# HandHeld_Terminal_V2_Rev3.net
KiCad netlist of a schematic drawn in Altium Designer
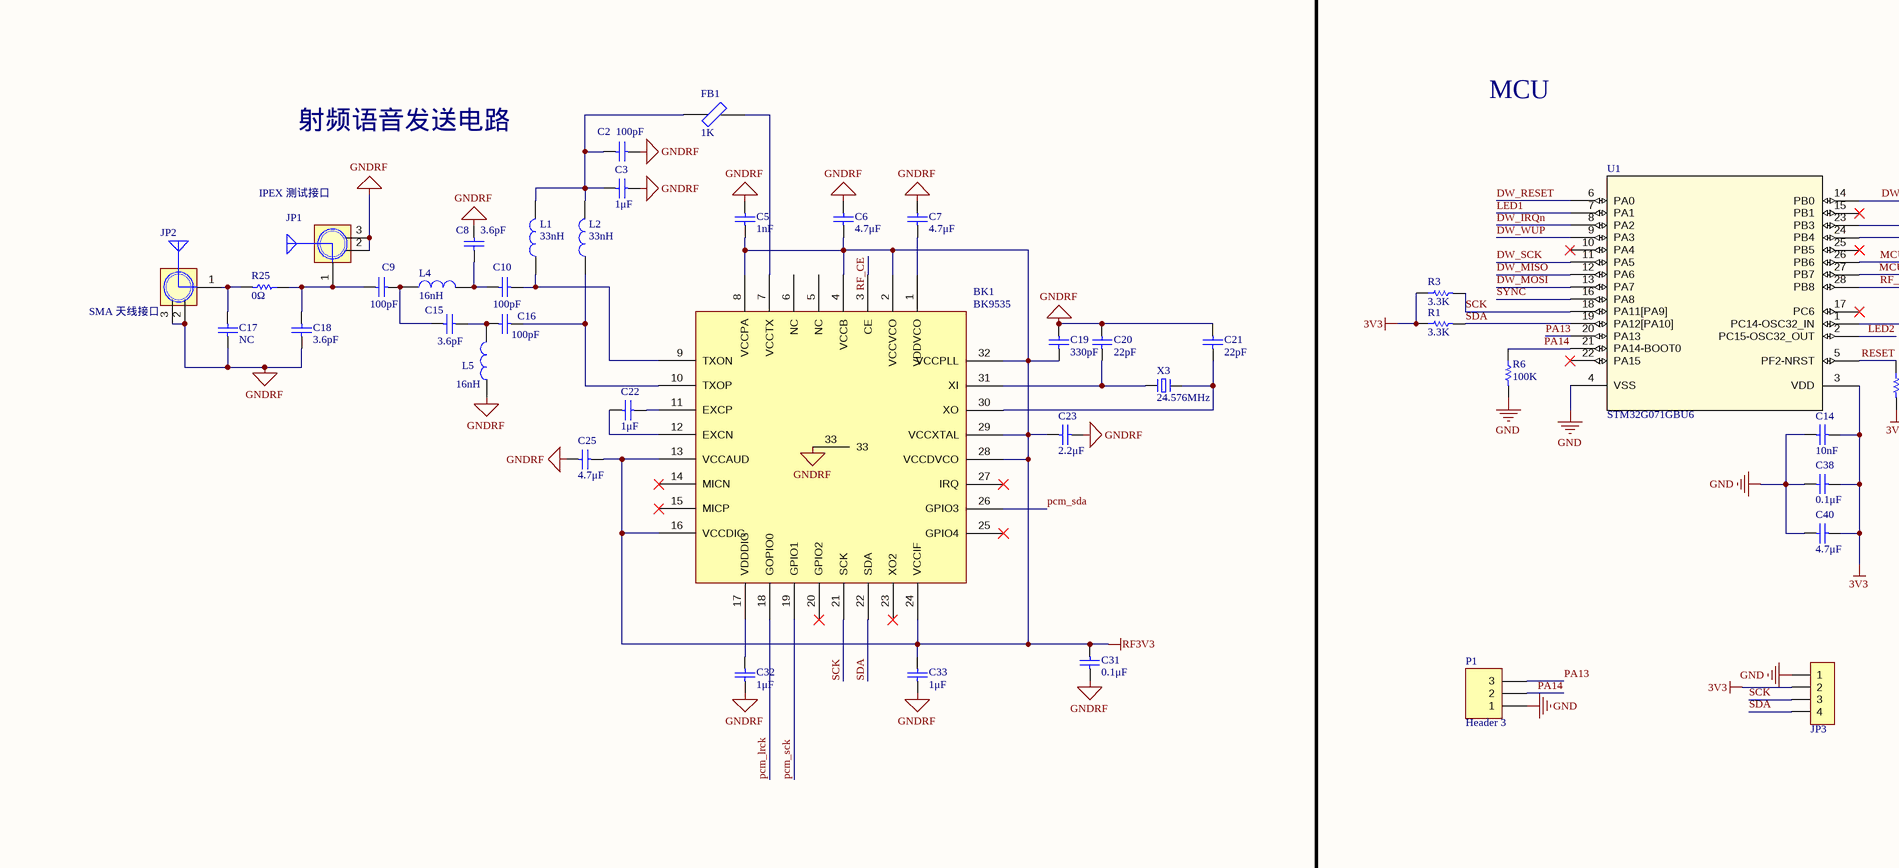
[diagram p0: HandHeld_Terminal_V2_Rev3.SchDoc, top left]
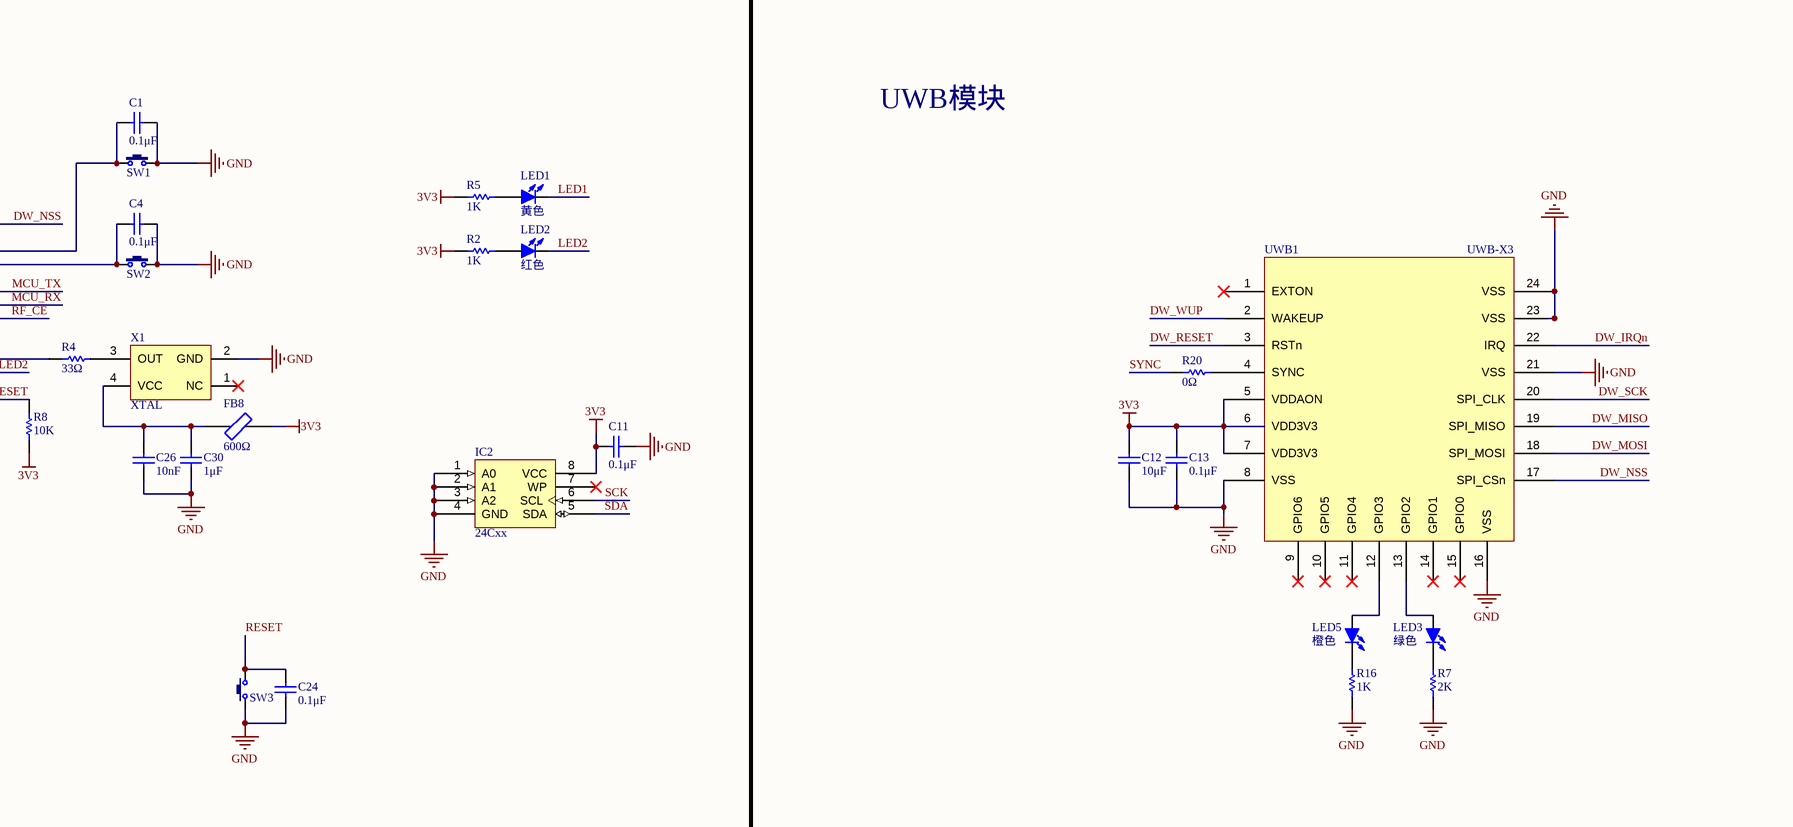
[diagram p1: HandHeld_Terminal_V2_Rev3.SchDoc, top right]
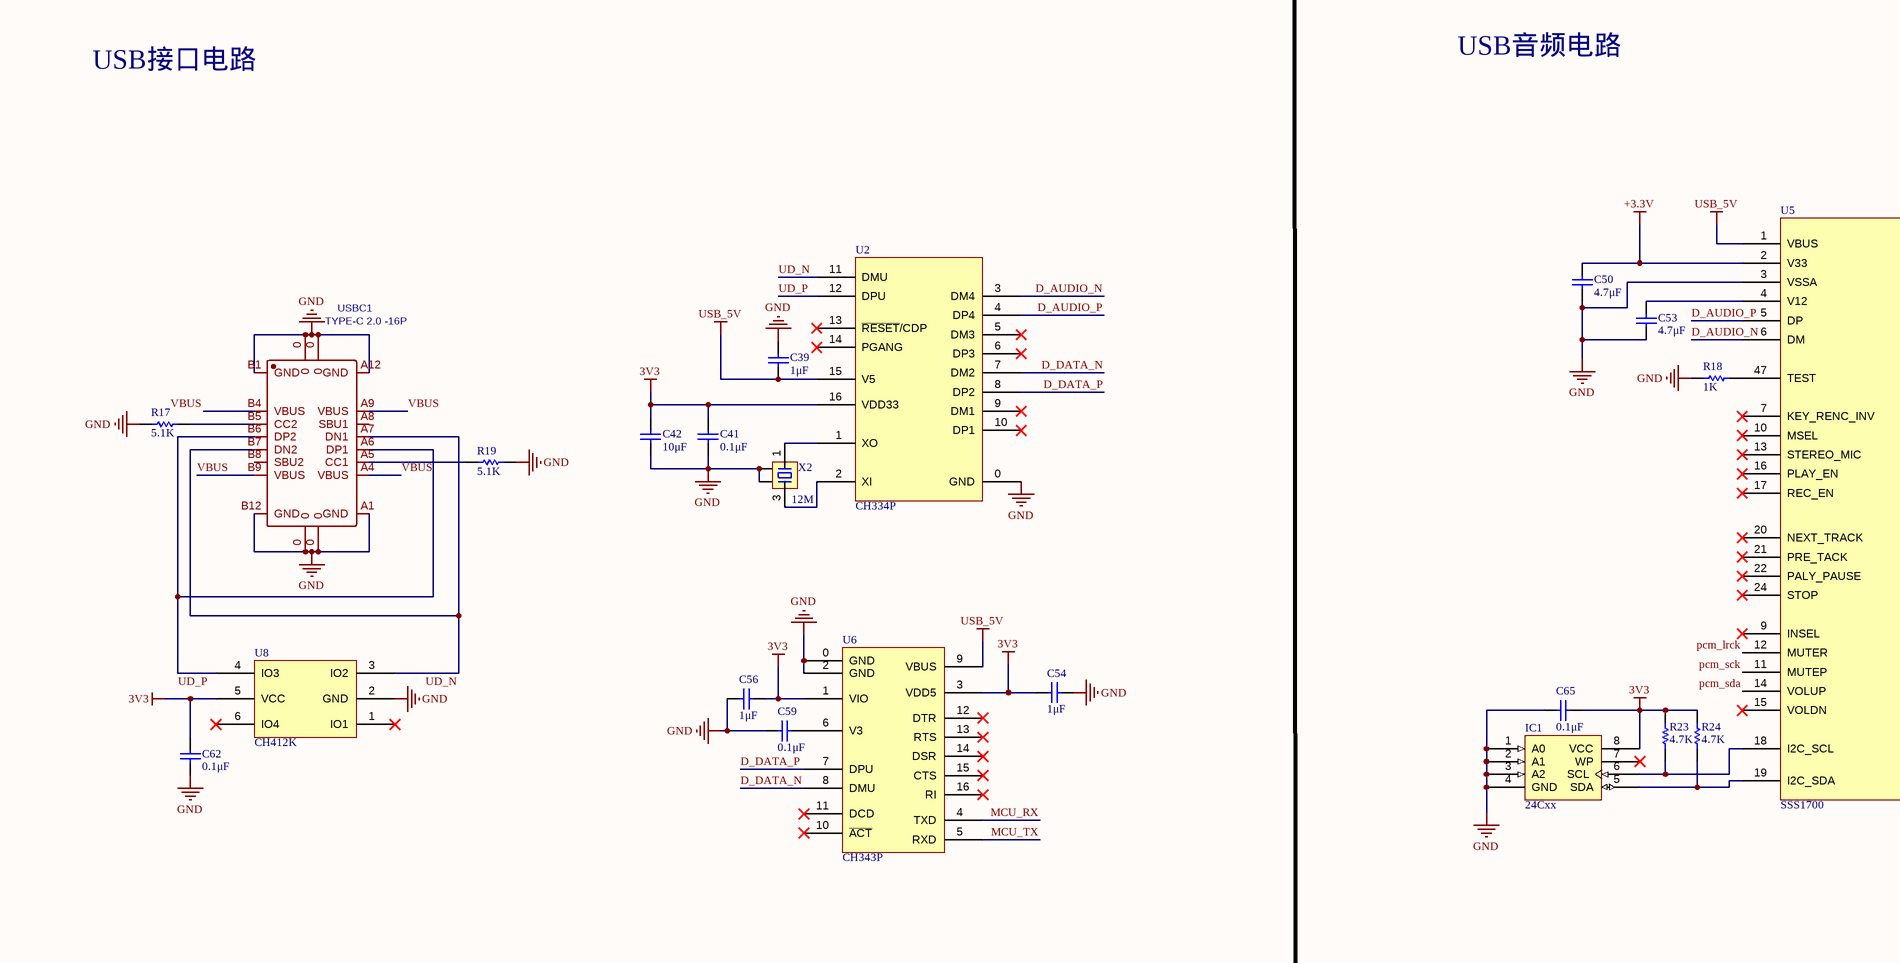
[diagram p2: HandHeld_Terminal_V2_Rev3.SchDoc, bottom left]
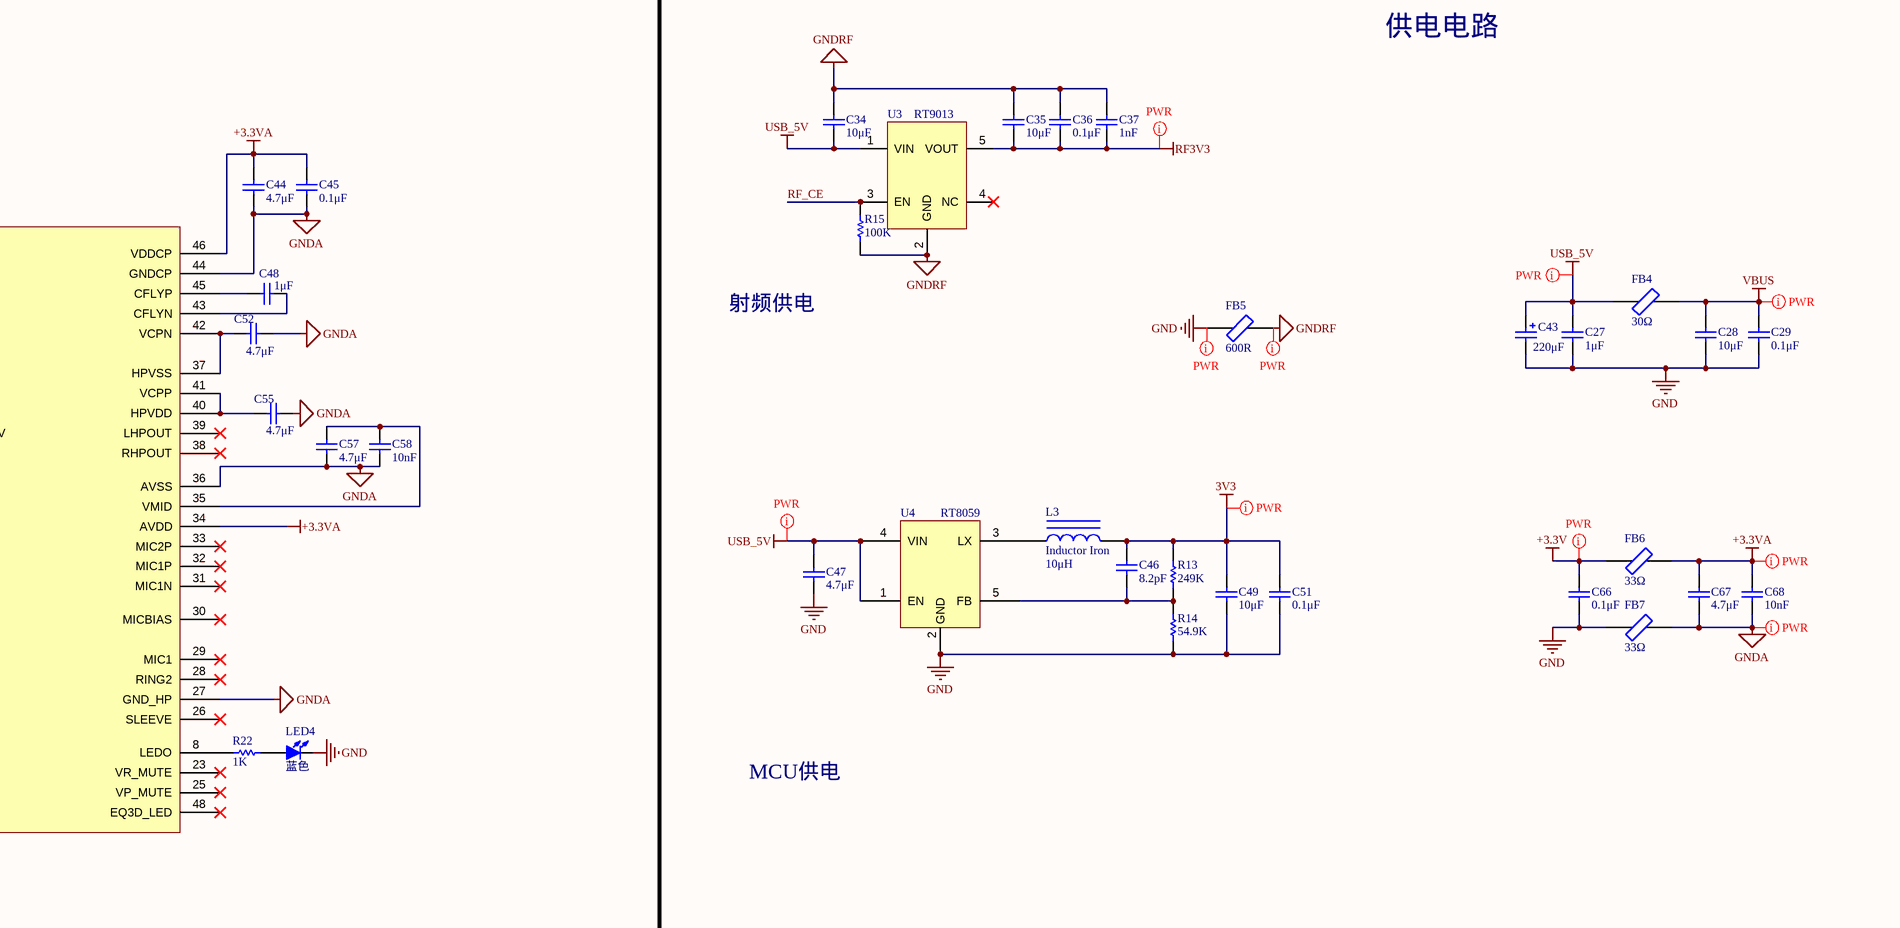
[diagram p3: HandHeld_Terminal_V2_Rev3.SchDoc, bottom right]

(export (version "E")
  (design (tool "Eeschema 10.0.6"))
  (components
    (comp (ref "BK1") (value "BK9535") (footprint "QFN32 5x5_N") (libsource (lib "Nixie") (part "BK9530")))
    (comp (ref "C1")
      (value "0.1μF")
      (footprint "C 0603_L")
      (description "Capacitor")
      (fields (field (name "Comment") "Cap") (field (name "PUBLISHER") "Altium Limited"))
      (libsource (lib "Nixie") (part "Cap"))
    )
    (comp (ref "C2")
      (value "100pF")
      (footprint "C 0603_L")
      (description "Capacitor")
      (fields (field (name "Comment") "Cap") (field (name "PUBLISHER") "Altium Limited"))
      (libsource (lib "Nixie") (part "Cap"))
    )
    (comp (ref "C3")
      (value "1μF")
      (footprint "C 0603_L")
      (description "Capacitor")
      (fields (field (name "Comment") "Cap") (field (name "PUBLISHER") "Altium Limited"))
      (libsource (lib "Nixie") (part "Cap"))
    )
    (comp (ref "C4")
      (value "0.1μF")
      (footprint "C 0603_L")
      (description "Capacitor")
      (fields (field (name "Comment") "Cap") (field (name "PUBLISHER") "Altium Limited"))
      (libsource (lib "Nixie") (part "Cap"))
    )
    (comp (ref "C5")
      (value "1nF")
      (footprint "C 0603_L")
      (description "Capacitor")
      (fields (field (name "Comment") "Cap") (field (name "PUBLISHER") "Altium Limited"))
      (libsource (lib "Nixie") (part "Cap"))
    )
    (comp (ref "C6")
      (value "4.7μF")
      (footprint "C 0603_L")
      (description "Capacitor")
      (fields (field (name "Comment") "Cap") (field (name "PUBLISHER") "Altium Limited"))
      (libsource (lib "Nixie") (part "Cap"))
    )
    (comp (ref "C7")
      (value "4.7μF")
      (footprint "C 0603_L")
      (description "Capacitor")
      (fields (field (name "Comment") "Cap") (field (name "PUBLISHER") "Altium Limited"))
      (libsource (lib "Nixie") (part "Cap"))
    )
    (comp (ref "C8")
      (value "3.6pF")
      (footprint "C 0603_L")
      (description "Capacitor")
      (fields (field (name "Comment") "Cap") (field (name "PUBLISHER") "Altium Limited"))
      (libsource (lib "Nixie") (part "Cap"))
    )
    (comp (ref "C9")
      (value "100pF")
      (footprint "C 0603_L")
      (description "Capacitor")
      (fields (field (name "Comment") "Cap") (field (name "PUBLISHER") "Altium Limited"))
      (libsource (lib "Nixie") (part "Cap"))
    )
    (comp (ref "C10")
      (value "100pF")
      (footprint "C 0603_L")
      (description "Capacitor")
      (fields (field (name "Comment") "Cap") (field (name "PUBLISHER") "Altium Limited"))
      (libsource (lib "Nixie") (part "Cap"))
    )
    (comp (ref "C11")
      (value "0.1μF")
      (footprint "C 0603_L")
      (description "Capacitor")
      (fields (field (name "Comment") "Cap") (field (name "PUBLISHER") "Altium Limited"))
      (libsource (lib "Nixie") (part "Cap"))
    )
    (comp (ref "C12")
      (value "10μF")
      (footprint "C 0603_L")
      (description "Capacitor")
      (fields (field (name "Comment") "Cap") (field (name "PUBLISHER") "Altium Limited"))
      (libsource (lib "Nixie") (part "Cap"))
    )
    (comp (ref "C13")
      (value "0.1μF")
      (footprint "C 0603_L")
      (description "Capacitor")
      (fields (field (name "Comment") "Cap") (field (name "PUBLISHER") "Altium Limited"))
      (libsource (lib "Nixie") (part "Cap"))
    )
    (comp (ref "C14")
      (value "10nF")
      (footprint "C 0603_L")
      (description "Capacitor")
      (fields (field (name "Comment") "Cap") (field (name "PUBLISHER") "Altium Limited"))
      (libsource (lib "Nixie") (part "Cap"))
    )
    (comp (ref "C15")
      (value "3.6pF")
      (footprint "C 0603_L")
      (description "Capacitor")
      (fields (field (name "Comment") "Cap") (field (name "PUBLISHER") "Altium Limited"))
      (libsource (lib "Nixie") (part "Cap"))
    )
    (comp (ref "C16")
      (value "100pF")
      (footprint "C 0603_L")
      (description "Capacitor")
      (fields (field (name "Comment") "Cap") (field (name "PUBLISHER") "Altium Limited"))
      (libsource (lib "Nixie") (part "Cap"))
    )
    (comp (ref "C17")
      (value "NC")
      (footprint "C 0603_L")
      (description "Capacitor")
      (fields (field (name "Comment") "Cap") (field (name "PUBLISHER") "Altium Limited"))
      (libsource (lib "Nixie") (part "Cap"))
    )
    (comp (ref "C18")
      (value "3.6pF")
      (footprint "C 0603_L")
      (description "Capacitor")
      (fields (field (name "Comment") "Cap") (field (name "PUBLISHER") "Altium Limited"))
      (libsource (lib "Nixie") (part "Cap"))
    )
    (comp (ref "C19")
      (value "330pF")
      (footprint "C 0603_L")
      (description "Capacitor")
      (fields (field (name "Comment") "Cap") (field (name "PUBLISHER") "Altium Limited"))
      (libsource (lib "Nixie") (part "Cap"))
    )
    (comp (ref "C20")
      (value "22pF")
      (footprint "C 0603_L")
      (description "Capacitor")
      (fields (field (name "Comment") "Cap") (field (name "PUBLISHER") "Altium Limited"))
      (libsource (lib "Nixie") (part "Cap"))
    )
    (comp (ref "C21")
      (value "22pF")
      (footprint "C 0603_L")
      (description "Capacitor")
      (fields (field (name "Comment") "Cap") (field (name "PUBLISHER") "Altium Limited"))
      (libsource (lib "Nixie") (part "Cap"))
    )
    (comp (ref "C22")
      (value "1μF")
      (footprint "C 0603_L")
      (description "Capacitor")
      (fields (field (name "Comment") "Cap") (field (name "PUBLISHER") "Altium Limited"))
      (libsource (lib "Nixie") (part "Cap"))
    )
    (comp (ref "C23")
      (value "2.2μF")
      (footprint "C 0603_L")
      (description "Capacitor")
      (fields (field (name "Comment") "Cap") (field (name "PUBLISHER") "Altium Limited"))
      (libsource (lib "Nixie") (part "Cap"))
    )
    (comp (ref "C24")
      (value "0.1μF")
      (footprint "C 0603_L")
      (description "Capacitor")
      (fields (field (name "Comment") "Cap") (field (name "PUBLISHER") "Altium Limited"))
      (libsource (lib "Nixie") (part "Cap"))
    )
    (comp (ref "C25")
      (value "4.7μF")
      (footprint "C 0603_L")
      (description "Capacitor")
      (fields (field (name "Comment") "Cap") (field (name "PUBLISHER") "Altium Limited"))
      (libsource (lib "Nixie") (part "Cap"))
    )
    (comp (ref "C26")
      (value "10nF")
      (footprint "C 0603_L")
      (description "Capacitor")
      (fields (field (name "Comment") "Cap") (field (name "PUBLISHER") "Altium Limited"))
      (libsource (lib "Nixie") (part "Cap"))
    )
    (comp (ref "C27")
      (value "1μF")
      (footprint "C 0603_L")
      (description "Capacitor")
      (fields (field (name "Comment") "Cap") (field (name "PUBLISHER") "Altium Limited"))
      (libsource (lib "Nixie") (part "Cap"))
    )
    (comp (ref "C28")
      (value "10μF")
      (footprint "C 0603_L")
      (description "Capacitor")
      (fields (field (name "Comment") "Cap") (field (name "PUBLISHER") "Altium Limited"))
      (libsource (lib "Nixie") (part "Cap"))
    )
    (comp (ref "C29")
      (value "0.1μF")
      (footprint "C 0603_L")
      (description "Capacitor")
      (fields (field (name "Comment") "Cap") (field (name "PUBLISHER") "Altium Limited"))
      (libsource (lib "Nixie") (part "Cap"))
    )
    (comp (ref "C30")
      (value "1μF")
      (footprint "C 0603_L")
      (description "Capacitor")
      (fields (field (name "Comment") "Cap") (field (name "PUBLISHER") "Altium Limited"))
      (libsource (lib "Nixie") (part "Cap"))
    )
    (comp (ref "C31")
      (value "0.1μF")
      (footprint "C 0603_L")
      (description "Capacitor")
      (fields (field (name "Comment") "Cap") (field (name "PUBLISHER") "Altium Limited"))
      (libsource (lib "Nixie") (part "Cap"))
    )
    (comp (ref "C32")
      (value "1μF")
      (footprint "C 0603_L")
      (description "Capacitor")
      (fields (field (name "Comment") "Cap") (field (name "PUBLISHER") "Altium Limited"))
      (libsource (lib "Nixie") (part "Cap"))
    )
    (comp (ref "C33")
      (value "1μF")
      (footprint "C 0603_L")
      (description "Capacitor")
      (fields (field (name "Comment") "Cap") (field (name "PUBLISHER") "Altium Limited"))
      (libsource (lib "Nixie") (part "Cap"))
    )
    (comp (ref "C34")
      (value "10μF")
      (footprint "C 0603_L")
      (description "Capacitor")
      (fields (field (name "Comment") "Cap") (field (name "PUBLISHER") "Altium Limited"))
      (libsource (lib "Nixie") (part "Cap"))
    )
    (comp (ref "C35")
      (value "10μF")
      (footprint "C 0603_L")
      (description "Capacitor")
      (fields (field (name "Comment") "Cap") (field (name "PUBLISHER") "Altium Limited"))
      (libsource (lib "Nixie") (part "Cap"))
    )
    (comp (ref "C36")
      (value "0.1μF")
      (footprint "C 0603_L")
      (description "Capacitor")
      (fields (field (name "Comment") "Cap") (field (name "PUBLISHER") "Altium Limited"))
      (libsource (lib "Nixie") (part "Cap"))
    )
    (comp (ref "C37")
      (value "1nF")
      (footprint "C 0603_L")
      (description "Capacitor")
      (fields (field (name "Comment") "Cap") (field (name "PUBLISHER") "Altium Limited"))
      (libsource (lib "Nixie") (part "Cap"))
    )
    (comp (ref "C38")
      (value "0.1μF")
      (footprint "C 0603_L")
      (description "Capacitor")
      (fields (field (name "Comment") "Cap") (field (name "PUBLISHER") "Altium Limited"))
      (libsource (lib "Nixie") (part "Cap"))
    )
    (comp (ref "C39")
      (value "1μF")
      (footprint "C 0603_L")
      (description "Capacitor")
      (fields (field (name "Comment") "Cap") (field (name "PUBLISHER") "Altium Limited"))
      (libsource (lib "Nixie") (part "Cap"))
    )
    (comp (ref "C40")
      (value "4.7μF")
      (footprint "C 0603_L")
      (description "Capacitor")
      (fields (field (name "Comment") "Cap") (field (name "PUBLISHER") "Altium Limited"))
      (libsource (lib "Nixie") (part "Cap"))
    )
    (comp (ref "C41")
      (value "0.1μF")
      (footprint "C 0603_L")
      (description "Capacitor")
      (fields (field (name "Comment") "Cap") (field (name "PUBLISHER") "Altium Limited"))
      (libsource (lib "Nixie") (part "Cap"))
    )
    (comp (ref "C42")
      (value "10μF")
      (footprint "C 0603_L")
      (description "Capacitor")
      (fields (field (name "Comment") "Cap") (field (name "PUBLISHER") "Altium Limited"))
      (libsource (lib "Nixie") (part "Cap"))
    )
    (comp (ref "C43")
      (value "220μF")
      (footprint "CM D(6.3*5.4)")
      (description "Polarized Capacitor (Radial)")
      (fields (field (name "Comment") "Cap Pol1") (field (name "PUBLISHER") "Altium Limited"))
      (libsource (lib "Nixie") (part "Cap Pol1"))
    )
    (comp (ref "C44")
      (value "4.7μF")
      (footprint "C 0603_L")
      (description "Capacitor")
      (fields (field (name "Comment") "Cap") (field (name "PUBLISHER") "Altium Limited"))
      (libsource (lib "Nixie") (part "Cap"))
    )
    (comp (ref "C45")
      (value "0.1μF")
      (footprint "C 0603_L")
      (description "Capacitor")
      (fields (field (name "Comment") "Cap") (field (name "PUBLISHER") "Altium Limited"))
      (libsource (lib "Nixie") (part "Cap"))
    )
    (comp (ref "C46")
      (value "8.2pF")
      (footprint "C 0603_L")
      (description "Capacitor")
      (fields (field (name "Comment") "Cap") (field (name "PUBLISHER") "Altium Limited"))
      (libsource (lib "Nixie") (part "Cap"))
    )
    (comp (ref "C47")
      (value "4.7μF")
      (footprint "C 0603_L")
      (description "Capacitor")
      (fields (field (name "Comment") "Cap") (field (name "PUBLISHER") "Altium Limited"))
      (libsource (lib "Nixie") (part "Cap"))
    )
    (comp (ref "C48")
      (value "1μF")
      (footprint "C 0603_L")
      (description "Capacitor")
      (fields (field (name "Comment") "Cap") (field (name "PUBLISHER") "Altium Limited"))
      (libsource (lib "Nixie") (part "Cap"))
    )
    (comp (ref "C49")
      (value "10μF")
      (footprint "C 0603_L")
      (description "Capacitor")
      (fields (field (name "Comment") "Cap") (field (name "PUBLISHER") "Altium Limited"))
      (libsource (lib "Nixie") (part "Cap"))
    )
    (comp (ref "C50")
      (value "4.7μF")
      (footprint "C 0603_L")
      (description "Capacitor")
      (fields (field (name "Comment") "Cap") (field (name "PUBLISHER") "Altium Limited"))
      (libsource (lib "Nixie") (part "Cap"))
    )
    (comp (ref "C51")
      (value "0.1μF")
      (footprint "C 0603_L")
      (description "Capacitor")
      (fields (field (name "Comment") "Cap") (field (name "PUBLISHER") "Altium Limited"))
      (libsource (lib "Nixie") (part "Cap"))
    )
    (comp (ref "C52")
      (value "4.7μF")
      (footprint "C 0603_L")
      (description "Capacitor")
      (fields (field (name "Comment") "Cap") (field (name "PUBLISHER") "Altium Limited"))
      (libsource (lib "Nixie") (part "Cap"))
    )
    (comp (ref "C53")
      (value "4.7μF")
      (footprint "C 0603_L")
      (description "Capacitor")
      (fields (field (name "Comment") "Cap") (field (name "PUBLISHER") "Altium Limited"))
      (libsource (lib "Nixie") (part "Cap"))
    )
    (comp (ref "C54")
      (value "1μF")
      (footprint "C 0603_L")
      (description "Capacitor")
      (fields (field (name "Comment") "Cap") (field (name "PUBLISHER") "Altium Limited"))
      (libsource (lib "Nixie") (part "Cap"))
    )
    (comp (ref "C55")
      (value "4.7μF")
      (footprint "C 0603_L")
      (description "Capacitor")
      (fields (field (name "Comment") "Cap") (field (name "PUBLISHER") "Altium Limited"))
      (libsource (lib "Nixie") (part "Cap"))
    )
    (comp (ref "C56")
      (value "1μF")
      (footprint "C 0603_L")
      (description "Capacitor")
      (fields (field (name "Comment") "Cap") (field (name "PUBLISHER") "Altium Limited"))
      (libsource (lib "Nixie") (part "Cap"))
    )
    (comp (ref "C57")
      (value "4.7μF")
      (footprint "C 0603_L")
      (description "Capacitor")
      (fields (field (name "Comment") "Cap") (field (name "PUBLISHER") "Altium Limited"))
      (libsource (lib "Nixie") (part "Cap"))
    )
    (comp (ref "C58")
      (value "10nF")
      (footprint "C 0603_L")
      (description "Capacitor")
      (fields (field (name "Comment") "Cap") (field (name "PUBLISHER") "Altium Limited"))
      (libsource (lib "Nixie") (part "Cap"))
    )
    (comp (ref "C59")
      (value "0.1μF")
      (footprint "C 0603_L")
      (description "Capacitor")
      (fields (field (name "Comment") "Cap") (field (name "PUBLISHER") "Altium Limited"))
      (libsource (lib "Nixie") (part "Cap"))
    )
    (comp (ref "C62")
      (value "0.1μF")
      (footprint "C 0603_L")
      (description "Capacitor")
      (fields (field (name "Comment") "Cap") (field (name "PUBLISHER") "Altium Limited"))
      (libsource (lib "Nixie") (part "Cap"))
    )
    (comp (ref "C65")
      (value "0.1μF")
      (footprint "C 0603_L")
      (description "Capacitor")
      (fields (field (name "Comment") "Cap") (field (name "PUBLISHER") "Altium Limited"))
      (libsource (lib "Nixie") (part "Cap"))
    )
    (comp (ref "C66")
      (value "0.1μF")
      (footprint "C 0603_L")
      (description "Capacitor")
      (fields (field (name "Comment") "Cap") (field (name "PUBLISHER") "Altium Limited"))
      (libsource (lib "Nixie") (part "Cap"))
    )
    (comp (ref "C67")
      (value "4.7μF")
      (footprint "C 0603_L")
      (description "Capacitor")
      (fields (field (name "Comment") "Cap") (field (name "PUBLISHER") "Altium Limited"))
      (libsource (lib "Nixie") (part "Cap"))
    )
    (comp (ref "C68")
      (value "10nF")
      (footprint "C 0603_L")
      (description "Capacitor")
      (fields (field (name "Comment") "Cap") (field (name "PUBLISHER") "Altium Limited"))
      (libsource (lib "Nixie") (part "Cap"))
    )
    (comp (ref "FB1")
      (value "1K")
      (footprint "C 0603_L")
      (description "铁氧体磁珠")
      (fields (field (name "Comment") "Ferrite bead"))
      (libsource (lib "Nixie") (part "Ferrite bead"))
    )
    (comp (ref "FB4")
      (value "30Ω")
      (footprint "C 0603_L")
      (description "铁氧体磁珠")
      (fields (field (name "Comment") "Ferrite bead"))
      (libsource (lib "Nixie") (part "Ferrite bead"))
    )
    (comp (ref "FB5")
      (value "600R")
      (footprint "C 0603_L")
      (description "铁氧体磁珠")
      (fields (field (name "Comment") "Ferrite bead"))
      (libsource (lib "Nixie") (part "Ferrite bead"))
    )
    (comp (ref "FB6")
      (value "33Ω")
      (footprint "C 0603_L")
      (description "铁氧体磁珠")
      (fields (field (name "Comment") "Ferrite bead"))
      (libsource (lib "Nixie") (part "Ferrite bead"))
    )
    (comp (ref "FB7")
      (value "33Ω")
      (footprint "C 0603_L")
      (description "铁氧体磁珠")
      (fields (field (name "Comment") "Ferrite bead"))
      (libsource (lib "Nixie") (part "Ferrite bead"))
    )
    (comp (ref "FB8")
      (value "600Ω")
      (footprint "C 0603_L")
      (description "铁氧体磁珠")
      (fields (field (name "Comment") "Ferrite bead"))
      (libsource (lib "Nixie") (part "Ferrite bead"))
    )
    (comp (ref "IC1")
      (value "24Cxx")
      (footprint "SOP8_L")
      (description "外置EEPROM")
      (fields (field (name "版权归属") "封装库来自淘宝 ID：黄晶宝石"))
      (libsource (lib "Nixie") (part "24Cxx"))
    )
    (comp (ref "IC2")
      (value "24Cxx")
      (footprint "SOP8_L")
      (description "外置EEPROM")
      (fields (field (name "版权归属") "封装库来自淘宝 ID：黄晶宝石"))
      (libsource (lib "Nixie") (part "24Cxx"))
    )
    (comp (ref "JP1")
      (value "IPEX 测试接口")
      (footprint "COAXIAL/SMD/CON/V/I-PEX/W08-5801")
      (description "SMA-2.4G射频天线接口")
      (fields (field (name "版权归属") "封装库来自淘宝 ID：黄晶宝石"))
      (libsource (lib "Nixie") (part "SMA"))
    )
    (comp (ref "JP2")
      (value "SMA 天线接口")
      (footprint "SMA-KE")
      (description "SMA-2.4G射频天线接口")
      (fields (field (name "版权归属") "封装库来自淘宝 ID：黄晶宝石"))
      (libsource (lib "") (part "SMA_1"))
    )
    (comp (ref "JP3")
      (value "HDR-1X4")
      (footprint "HDR2.54-LI-4P")
      (description "4P接插件")
      (fields (field (name "版权归属") "封装库来自淘宝 ID：黄晶宝石"))
      (libsource (lib "Nixie") (part "Header 4"))
    )
    (comp (ref "L1")
      (value "33nH")
      (footprint "L 0603")
      (description "小功率贴片电感")
      (fields (field (name "Comment") "L"))
      (libsource (lib "Nixie") (part "L"))
    )
    (comp (ref "L2")
      (value "33nH")
      (footprint "L 0603")
      (description "小功率贴片电感")
      (fields (field (name "Comment") "L"))
      (libsource (lib "Nixie") (part "L"))
    )
    (comp (ref "L3")
      (value "Inductor Iron")
      (footprint "NR4018")
      (description "Magnetic-Core Inductor")
      (fields (field (name "ALTIUM_VALUE") "10μH") (field (name "PUBLISHER") "Altium Limited"))
      (libsource (lib "Nixie") (part "Inductor Iron"))
    )
    (comp (ref "L4")
      (value "16nH")
      (footprint "L 0603")
      (description "小功率贴片电感")
      (fields (field (name "Comment") "L"))
      (libsource (lib "Nixie") (part "L"))
    )
    (comp (ref "L5")
      (value "16nH")
      (footprint "L 0603")
      (description "小功率贴片电感")
      (fields (field (name "Comment") "L"))
      (libsource (lib "Nixie") (part "L"))
    )
    (comp (ref "LED1")
      (value "黄色")
      (footprint "LED 0805G")
      (description "贴片LED")
      (fields (field (name "版权归属") "封装库来自淘宝 ID：黄晶宝石"))
      (libsource (lib "Nixie") (part "LED-SMD"))
    )
    (comp (ref "LED2")
      (value "红色")
      (footprint "LED 0805R")
      (description "贴片LED")
      (fields (field (name "版权归属") "封装库来自淘宝 ID：黄晶宝石"))
      (libsource (lib "Nixie") (part "LED-SMD"))
    )
    (comp (ref "LED3")
      (value "绿色")
      (footprint "LED 0805G")
      (description "贴片LED")
      (fields (field (name "版权归属") "封装库来自淘宝 ID：黄晶宝石"))
      (libsource (lib "Nixie") (part "LED-SMD"))
    )
    (comp (ref "LED4")
      (value "蓝色")
      (footprint "LED 0805B")
      (description "贴片LED")
      (fields (field (name "版权归属") "封装库来自淘宝 ID：黄晶宝石"))
      (libsource (lib "Nixie") (part "LED-SMD"))
    )
    (comp (ref "LED5")
      (value "橙色")
      (footprint "LED 0805G")
      (description "贴片LED")
      (fields (field (name "版权归属") "封装库来自淘宝 ID：黄晶宝石"))
      (libsource (lib "Nixie") (part "LED-SMD"))
    )
    (comp (ref "P1")
      (value "Header 3")
      (footprint "HDR2.54-LI-3P")
      (description "Header, 3-Pin")
      (fields (field (name "PUBLISHER") "Altium Limited"))
      (libsource (lib "Miscellaneous Connectors") (part "Header 3"))
    )
    (comp (ref "R1")
      (value "3.3K")
      (footprint "R 0603_L")
      (description "Resistor")
      (fields (field (name "PUBLISHER") "Altium Limited"))
      (libsource (lib "Nixie") (part "Resistor"))
    )
    (comp (ref "R2")
      (value "1K")
      (footprint "R 0603_L")
      (description "Resistor")
      (fields (field (name "PUBLISHER") "Altium Limited"))
      (libsource (lib "Nixie") (part "Resistor"))
    )
    (comp (ref "R3")
      (value "3.3K")
      (footprint "R 0603_L")
      (description "Resistor")
      (fields (field (name "PUBLISHER") "Altium Limited"))
      (libsource (lib "Nixie") (part "Resistor"))
    )
    (comp (ref "R4")
      (value "33Ω")
      (footprint "R 0603_L")
      (description "Resistor")
      (fields (field (name "PUBLISHER") "Altium Limited"))
      (libsource (lib "Nixie") (part "Resistor"))
    )
    (comp (ref "R5")
      (value "1K")
      (footprint "R 0603_L")
      (description "Resistor")
      (fields (field (name "PUBLISHER") "Altium Limited"))
      (libsource (lib "Nixie") (part "Resistor"))
    )
    (comp (ref "R6")
      (value "100K")
      (footprint "R 0603_L")
      (description "Resistor")
      (fields (field (name "PUBLISHER") "Altium Limited"))
      (libsource (lib "Nixie") (part "Resistor"))
    )
    (comp (ref "R7")
      (value "2K")
      (footprint "R 0603_L")
      (description "Resistor")
      (fields (field (name "PUBLISHER") "Altium Limited"))
      (libsource (lib "Nixie") (part "Resistor"))
    )
    (comp (ref "R8")
      (value "10K")
      (footprint "R 0603_L")
      (description "Resistor")
      (fields (field (name "PUBLISHER") "Altium Limited"))
      (libsource (lib "Nixie") (part "Resistor"))
    )
    (comp (ref "R13")
      (value "249K")
      (footprint "R 0603_L")
      (description "Resistor")
      (fields (field (name "PUBLISHER") "Altium Limited"))
      (libsource (lib "Nixie") (part "Resistor"))
    )
    (comp (ref "R14")
      (value "54.9K")
      (footprint "R 0603_L")
      (description "Resistor")
      (fields (field (name "PUBLISHER") "Altium Limited"))
      (libsource (lib "Nixie") (part "Resistor"))
    )
    (comp (ref "R15")
      (value "100K")
      (footprint "R 0603_L")
      (description "Resistor")
      (fields (field (name "PUBLISHER") "Altium Limited"))
      (libsource (lib "Nixie") (part "Resistor"))
    )
    (comp (ref "R16")
      (value "1K")
      (footprint "R 0603_L")
      (description "Resistor")
      (fields (field (name "PUBLISHER") "Altium Limited"))
      (libsource (lib "Nixie") (part "Resistor"))
    )
    (comp (ref "R17")
      (value "5.1K")
      (footprint "R 0603_L")
      (description "Resistor")
      (fields (field (name "PUBLISHER") "Altium Limited"))
      (libsource (lib "Nixie") (part "Resistor"))
    )
    (comp (ref "R18")
      (value "1K")
      (footprint "R 0603_L")
      (description "Resistor")
      (fields (field (name "PUBLISHER") "Altium Limited"))
      (libsource (lib "Nixie") (part "Resistor"))
    )
    (comp (ref "R19")
      (value "5.1K")
      (footprint "R 0603_L")
      (description "Resistor")
      (fields (field (name "PUBLISHER") "Altium Limited"))
      (libsource (lib "Nixie") (part "Resistor"))
    )
    (comp (ref "R20")
      (value "0Ω")
      (footprint "R 0603_L")
      (description "Resistor")
      (fields (field (name "PUBLISHER") "Altium Limited"))
      (libsource (lib "Nixie") (part "Resistor"))
    )
    (comp (ref "R22")
      (value "1K")
      (footprint "R 0603_L")
      (description "Resistor")
      (fields (field (name "PUBLISHER") "Altium Limited"))
      (libsource (lib "Nixie") (part "Resistor"))
    )
    (comp (ref "R23")
      (value "4.7K")
      (footprint "R 0603_L")
      (description "Resistor")
      (fields (field (name "PUBLISHER") "Altium Limited"))
      (libsource (lib "Nixie") (part "Resistor"))
    )
    (comp (ref "R24")
      (value "4.7K")
      (footprint "R 0603_L")
      (description "Resistor")
      (fields (field (name "PUBLISHER") "Altium Limited"))
      (libsource (lib "Nixie") (part "Resistor"))
    )
    (comp (ref "R25")
      (value "0Ω")
      (footprint "R 0603_L")
      (description "Resistor")
      (fields (field (name "PUBLISHER") "Altium Limited"))
      (libsource (lib "Nixie") (part "Resistor"))
    )
    (comp (ref "SW1")
      (value "3x6x5")
      (footprint "TSW SMD-3*6*2.5")
      (description "3x6轻触开关")
      (fields (field (name "版权归属") "封装库来自淘宝 ID：黄晶宝石"))
      (libsource (lib "Nixie") (part "TSW 3x6"))
    )
    (comp (ref "SW2")
      (value "3x6x5")
      (footprint "TSW SMD-3*6*2.5")
      (description "3x6轻触开关")
      (fields (field (name "版权归属") "封装库来自淘宝 ID：黄晶宝石"))
      (libsource (lib "Nixie") (part "TSW 3x6"))
    )
    (comp (ref "SW3")
      (value "3x6x5")
      (footprint "TSW SMD-3*6*2.5")
      (description "3x6轻触开关")
      (fields (field (name "版权归属") "封装库来自淘宝 ID：黄晶宝石"))
      (libsource (lib "") (part "TSW 3x6_1"))
    )
    (comp (ref "U1")
      (value "STM32G071GBU6")
      (footprint "UFQFPN-28")
      (description "No Description Available")
      (libsource (lib "Nixie") (part "STM32G071GBU6"))
    )
    (comp (ref "U2")
      (value "CH334P")
      (footprint "QFN16")
      (description "4路usb_hub")
      (libsource (lib "Nixie") (part "CH334"))
    )
    (comp (ref "U3")
      (value "RT9013")
      (footprint "SOT23-5L")
      (description "LDO")
      (libsource (lib "HandHeld_terminal") (part "RT9013"))
    )
    (comp (ref "U4")
      (value "RT8059")
      (footprint "SOT23-5L")
      (description "DC-DC, 2.8-5.5V,1A")
      (libsource (lib "Nixie") (part "RT8059"))
    )
    (comp (ref "U5")
      (value "SSS1700")
      (footprint "LQFP48_L")
      (description "USB音频芯片")
      (libsource (lib "Nixie") (part "SSS1700"))
    )
    (comp (ref "U6")
      (value "CH343P")
      (footprint "QFN16")
      (description "USB转串口")
      (libsource (lib "Nixie") (part "CH343"))
    )
    (comp (ref "U8")
      (value "CH412K")
      (footprint "SOT-363")
      (description "四路ESD保护")
      (libsource (lib "Nixie") (part "CH412K"))
    )
    (comp (ref "USBC1")
      (value "TYPE-C 2.0 -16P")
      (footprint "USB-C-SMD_TYPE-C-USB-5")
      (description "USB2.0 Type-C 母座 16Pin")
      (libsource (lib "Nixie") (part "USB2.0 Type-C 16Pin母座"))
    )
    (comp (ref "UWB1")
      (value "UWB-X3")
      (footprint "UWB-X3-MAX-IPEX")
      (libsource (lib "Nixie") (part "UWB-X3(DWM3000)"))
    )
    (comp (ref "X1")
      (value "XTAL")
      (footprint "OSC 3225-4P")
      (description "4脚有源晶振")
      (libsource (lib "Nixie") (part "XTAL"))
    )
    (comp (ref "X2")
      (value "12M")
      (footprint "OSC 3225-4P")
      (description "4脚无源晶振")
      (fields (field (name "版权归属") "封装库来自淘宝卖家 ID：黄晶宝石"))
      (libsource (lib "Nixie") (part "XTAL-4P"))
    )
    (comp (ref "X3")
      (value "24.576MHz")
      (footprint "OSC 5032-2P")
      (description "2脚无源脚晶振")
      (fields (field (name "版权归属") "封装库来自淘宝卖家 ID：黄晶宝石"))
      (libsource (lib "Nixie") (part "XTAL-2P"))
    )
  )
  (nets
    (net (code "1") (name "+3.3V") (class "Default")
      (node (ref "C50") (pin "2") (pinfunction "2_2") (pintype "passive"))
      (node (ref "C66") (pin "2") (pinfunction "2_2") (pintype "passive"))
      (node (ref "FB6") (pin "1") (pinfunction "1_1") (pintype "passive"))
      (node (ref "U5") (pin "2") (pinfunction "V33_2") (pintype "passive"))
    )
    (net (code "2") (name "+3.3VA") (class "Default")
      (node (ref "C44") (pin "2") (pinfunction "2_2") (pintype "passive"))
      (node (ref "C45") (pin "2") (pinfunction "2_2") (pintype "passive"))
      (node (ref "C67") (pin "2") (pinfunction "2_2") (pintype "passive"))
      (node (ref "C68") (pin "2") (pinfunction "2_2") (pintype "passive"))
      (node (ref "FB6") (pin "2") (pinfunction "2_2") (pintype "passive"))
      (node (ref "U5") (pin "34") (pinfunction "AVDD_34") (pintype "passive"))
      (node (ref "U5") (pin "46") (pinfunction "VDDCP_46") (pintype "passive"))
    )
    (net (code "3") (name "/DW_IRQn") (class "Default")
      (node (ref "U1") (pin "8") (pinfunction "PA2_8") (pintype "bidirectional"))
      (node (ref "UWB1") (pin "22") (pinfunction "IRQ_22") (pintype "passive"))
    )
    (net (code "4") (name "/DW_MISO") (class "Default")
      (node (ref "U1") (pin "12") (pinfunction "PA6_12") (pintype "bidirectional"))
      (node (ref "UWB1") (pin "19") (pinfunction "SPI_MISO_19") (pintype "passive"))
    )
    (net (code "5") (name "/DW_MOSI") (class "Default")
      (node (ref "U1") (pin "13") (pinfunction "PA7_13") (pintype "bidirectional"))
      (node (ref "UWB1") (pin "18") (pinfunction "SPI_MOSI_18") (pintype "passive"))
    )
    (net (code "6") (name "/DW_NSS") (class "Default")
      (node (ref "U1") (pin "14") (pinfunction "PB0_14") (pintype "bidirectional"))
      (node (ref "UWB1") (pin "17") (pinfunction "SPI_CSn_17") (pintype "passive"))
    )
    (net (code "7") (name "/DW_RESET") (class "Default")
      (node (ref "U1") (pin "6") (pinfunction "PA0_6") (pintype "bidirectional"))
      (node (ref "UWB1") (pin "3") (pinfunction "RSTn_3") (pintype "passive"))
    )
    (net (code "8") (name "/DW_SCK") (class "Default")
      (node (ref "U1") (pin "11") (pinfunction "PA5_11") (pintype "bidirectional"))
      (node (ref "UWB1") (pin "20") (pinfunction "SPI_CLK_20") (pintype "passive"))
    )
    (net (code "9") (name "/DW_WUP") (class "Default")
      (node (ref "U1") (pin "9") (pinfunction "PA3_9") (pintype "bidirectional"))
      (node (ref "UWB1") (pin "2") (pinfunction "WAKEUP_2") (pintype "passive"))
    )
    (net (code "10") (name "/D_AUDIO_N") (class "Default")
      (node (ref "U2") (pin "3") (pinfunction "DM4_3") (pintype "passive"))
      (node (ref "U5") (pin "6") (pinfunction "DM_6") (pintype "passive"))
    )
    (net (code "11") (name "/D_AUDIO_P") (class "Default")
      (node (ref "U2") (pin "4") (pinfunction "DP4_4") (pintype "passive"))
      (node (ref "U5") (pin "5") (pinfunction "DP_5") (pintype "passive"))
    )
    (net (code "12") (name "/D_DATA_N") (class "Default")
      (node (ref "U2") (pin "7") (pinfunction "DM2_7") (pintype "passive"))
      (node (ref "U6") (pin "8") (pinfunction "DMU_8") (pintype "passive"))
    )
    (net (code "13") (name "/D_DATA_P") (class "Default")
      (node (ref "U2") (pin "8") (pinfunction "DP2_8") (pintype "passive"))
      (node (ref "U6") (pin "7") (pinfunction "DPU_7") (pintype "passive"))
    )
    (net (code "14") (name "/LED1") (class "Default")
      (node (ref "LED1") (pin "2") (pinfunction "K_2") (pintype "passive"))
      (node (ref "U1") (pin "7") (pinfunction "PA1_7") (pintype "bidirectional"))
    )
    (net (code "15") (name "/LED2") (class "Default")
      (node (ref "LED2") (pin "2") (pinfunction "K_2") (pintype "passive"))
      (node (ref "U1") (pin "2") (pinfunction "PC15-OSC32_OUT_2") (pintype "bidirectional"))
    )
    (net (code "16") (name "/MCU_RX") (class "Default")
      (node (ref "U1") (pin "27") (pinfunction "PB7_27") (pintype "bidirectional"))
      (node (ref "U6") (pin "4") (pinfunction "TXD_4") (pintype "passive"))
    )
    (net (code "17") (name "/MCU_TX") (class "Default")
      (node (ref "U1") (pin "26") (pinfunction "PB6_26") (pintype "bidirectional"))
      (node (ref "U6") (pin "5") (pinfunction "RXD_5") (pintype "passive"))
    )
    (net (code "18") (name "/PA13") (class "Default")
      (node (ref "P1") (pin "3") (pinfunction "3_3") (pintype "passive"))
      (node (ref "U1") (pin "20") (pinfunction "PA13_20") (pintype "bidirectional"))
    )
    (net (code "19") (name "/PA14") (class "Default")
      (node (ref "P1") (pin "2") (pinfunction "2_2") (pintype "passive"))
      (node (ref "R6") (pin "1") (pinfunction "1_1") (pintype "passive"))
      (node (ref "U1") (pin "21") (pinfunction "PA14-BOOT0_21") (pintype "bidirectional"))
    )
    (net (code "20") (name "/RESET") (class "Default")
      (node (ref "C24") (pin "2") (pinfunction "2_2") (pintype "passive"))
      (node (ref "R8") (pin "1") (pinfunction "1_1") (pintype "passive"))
      (node (ref "SW3") (pin "2") (pinfunction "2_2") (pintype "passive"))
      (node (ref "U1") (pin "5") (pinfunction "PF2-NRST_5") (pintype "bidirectional"))
    )
    (net (code "21") (name "/RF_CE") (class "Default")
      (node (ref "BK1") (pin "3") (pinfunction "CE_3") (pintype "passive"))
      (node (ref "R15") (pin "2") (pinfunction "2_2") (pintype "passive"))
      (node (ref "U1") (pin "28") (pinfunction "PB8_28") (pintype "bidirectional"))
      (node (ref "U3") (pin "3") (pinfunction "EN_3") (pintype "passive"))
    )
    (net (code "22") (name "/SCK") (class "Default")
      (node (ref "BK1") (pin "21") (pinfunction "SCK_21") (pintype "passive"))
      (node (ref "IC2") (pin "6") (pinfunction "SCL_6") (pintype "input"))
      (node (ref "JP3") (pin "3") (pinfunction "3_3") (pintype "passive"))
      (node (ref "R3") (pin "2") (pinfunction "2_2") (pintype "passive"))
      (node (ref "U1") (pin "18") (pinfunction "PA11[PA9]_18") (pintype "bidirectional"))
    )
    (net (code "23") (name "/SDA") (class "Default")
      (node (ref "BK1") (pin "22") (pinfunction "SDA_22") (pintype "passive"))
      (node (ref "IC2") (pin "5") (pinfunction "SDA_5") (pintype "bidirectional"))
      (node (ref "JP3") (pin "4") (pinfunction "4_4") (pintype "passive"))
      (node (ref "R1") (pin "2") (pinfunction "2_2") (pintype "passive"))
      (node (ref "U1") (pin "19") (pinfunction "PA12[PA10]_19") (pintype "bidirectional"))
    )
    (net (code "24") (name "/SYNC") (class "Default")
      (node (ref "R20") (pin "1") (pinfunction "1_1") (pintype "passive"))
      (node (ref "U1") (pin "16") (pinfunction "PA8_16") (pintype "bidirectional"))
    )
    (net (code "25") (name "/UD_N") (class "Default")
      (node (ref "U2") (pin "11") (pinfunction "DMU_11") (pintype "passive"))
      (node (ref "U8") (pin "3") (pinfunction "IO2_3") (pintype "passive"))
      (node (ref "USBC1") (pin "A7") (pinfunction "DN1_A7") (pintype "passive"))
      (node (ref "USBC1") (pin "B7") (pinfunction "DN2_B7") (pintype "passive"))
    )
    (net (code "26") (name "/UD_P") (class "Default")
      (node (ref "U2") (pin "12") (pinfunction "DPU_12") (pintype "passive"))
      (node (ref "U8") (pin "4") (pinfunction "IO3_4") (pintype "passive"))
      (node (ref "USBC1") (pin "A6") (pinfunction "DP1_A6") (pintype "passive"))
      (node (ref "USBC1") (pin "B6") (pinfunction "DP2_B6") (pintype "passive"))
    )
    (net (code "27") (name "/pcm_lrck") (class "Default")
      (node (ref "BK1") (pin "18") (pinfunction "GOPIO0_18") (pintype "passive"))
      (node (ref "U5") (pin "12") (pinfunction "MUTER_12") (pintype "passive"))
    )
    (net (code "28") (name "/pcm_sck") (class "Default")
      (node (ref "BK1") (pin "19") (pinfunction "GPIO1_19") (pintype "passive"))
      (node (ref "U5") (pin "11") (pinfunction "MUTEP_11") (pintype "passive"))
    )
    (net (code "29") (name "/pcm_sda") (class "Default")
      (node (ref "BK1") (pin "26") (pinfunction "GPIO3_26") (pintype "passive"))
      (node (ref "U5") (pin "14") (pinfunction "VOLUP_14") (pintype "passive"))
    )
    (net (code "30") (name "3V3") (class "Default")
      (node (ref "C11") (pin "2") (pinfunction "2_2") (pintype "passive"))
      (node (ref "C12") (pin "1") (pinfunction "1_1") (pintype "passive"))
      (node (ref "C13") (pin "1") (pinfunction "1_1") (pintype "passive"))
      (node (ref "C14") (pin "2") (pinfunction "2_2") (pintype "passive"))
      (node (ref "C38") (pin "2") (pinfunction "2_2") (pintype "passive"))
      (node (ref "C40") (pin "1") (pinfunction "1_1") (pintype "passive"))
      (node (ref "C41") (pin "1") (pinfunction "1_1") (pintype "passive"))
      (node (ref "C42") (pin "2") (pinfunction "2_2") (pintype "passive"))
      (node (ref "C46") (pin "1") (pinfunction "1_1") (pintype "passive"))
      (node (ref "C49") (pin "1") (pinfunction "1_1") (pintype "passive"))
      (node (ref "C51") (pin "1") (pinfunction "1_1") (pintype "passive"))
      (node (ref "C54") (pin "1") (pinfunction "1_1") (pintype "passive"))
      (node (ref "C56") (pin "2") (pinfunction "2_2") (pintype "passive"))
      (node (ref "C62") (pin "2") (pinfunction "2_2") (pintype "passive"))
      (node (ref "C65") (pin "1") (pinfunction "1_1") (pintype "passive"))
      (node (ref "FB8") (pin "2") (pinfunction "2_2") (pintype "passive"))
      (node (ref "IC1") (pin "8") (pinfunction "VCC_8") (pintype "power_in"))
      (node (ref "IC2") (pin "8") (pinfunction "VCC_8") (pintype "power_in"))
      (node (ref "JP3") (pin "2") (pinfunction "2_2") (pintype "passive"))
      (node (ref "L3") (pin "2") (pinfunction "2_2") (pintype "passive"))
      (node (ref "R1") (pin "1") (pinfunction "1_1") (pintype "passive"))
      (node (ref "R13") (pin "2") (pinfunction "2_2") (pintype "passive"))
      (node (ref "R2") (pin "2") (pinfunction "2_2") (pintype "passive"))
      (node (ref "R23") (pin "2") (pinfunction "2_2") (pintype "passive"))
      (node (ref "R24") (pin "2") (pinfunction "2_2") (pintype "passive"))
      (node (ref "R3") (pin "1") (pinfunction "1_1") (pintype "passive"))
      (node (ref "R5") (pin "2") (pinfunction "2_2") (pintype "passive"))
      (node (ref "R8") (pin "2") (pinfunction "2_2") (pintype "passive"))
      (node (ref "U1") (pin "3") (pinfunction "VDD_3") (pintype "power_in"))
      (node (ref "U2") (pin "16") (pinfunction "VDD33_16") (pintype "passive"))
      (node (ref "U6") (pin "1") (pinfunction "VIO_1") (pintype "passive"))
      (node (ref "U6") (pin "3") (pinfunction "VDD5_3") (pintype "passive"))
      (node (ref "U8") (pin "5") (pinfunction "VCC_5") (pintype "passive"))
      (node (ref "UWB1") (pin "5") (pinfunction "VDDAON_5") (pintype "passive"))
      (node (ref "UWB1") (pin "6") (pinfunction "VDD3V3_6") (pintype "passive"))
      (node (ref "UWB1") (pin "7") (pinfunction "VDD3V3_7") (pintype "passive"))
    )
    (net (code "31") (name "GND") (class "Default")
      (node (ref "C1") (pin "1") (pinfunction "1_1") (pintype "passive"))
      (node (ref "C11") (pin "1") (pinfunction "1_1") (pintype "passive"))
      (node (ref "C12") (pin "2") (pinfunction "2_2") (pintype "passive"))
      (node (ref "C13") (pin "2") (pinfunction "2_2") (pintype "passive"))
      (node (ref "C14") (pin "1") (pinfunction "1_1") (pintype "passive"))
      (node (ref "C24") (pin "1") (pinfunction "1_1") (pintype "passive"))
      (node (ref "C26") (pin "1") (pinfunction "1_1") (pintype "passive"))
      (node (ref "C27") (pin "1") (pinfunction "1_1") (pintype "passive"))
      (node (ref "C28") (pin "1") (pinfunction "1_1") (pintype "passive"))
      (node (ref "C29") (pin "1") (pinfunction "1_1") (pintype "passive"))
      (node (ref "C30") (pin "1") (pinfunction "1_1") (pintype "passive"))
      (node (ref "C38") (pin "1") (pinfunction "1_1") (pintype "passive"))
      (node (ref "C39") (pin "1") (pinfunction "1_1") (pintype "passive"))
      (node (ref "C4") (pin "1") (pinfunction "1_1") (pintype "passive"))
      (node (ref "C40") (pin "2") (pinfunction "2_2") (pintype "passive"))
      (node (ref "C41") (pin "2") (pinfunction "2_2") (pintype "passive"))
      (node (ref "C42") (pin "1") (pinfunction "1_1") (pintype "passive"))
      (node (ref "C43") (pin "2") (pinfunction "2_2") (pintype "passive"))
      (node (ref "C47") (pin "2") (pinfunction "2_2") (pintype "passive"))
      (node (ref "C49") (pin "2") (pinfunction "2_2") (pintype "passive"))
      (node (ref "C50") (pin "1") (pinfunction "1_1") (pintype "passive"))
      (node (ref "C51") (pin "2") (pinfunction "2_2") (pintype "passive"))
      (node (ref "C53") (pin "1") (pinfunction "1_1") (pintype "passive"))
      (node (ref "C54") (pin "2") (pinfunction "2_2") (pintype "passive"))
      (node (ref "C56") (pin "1") (pinfunction "1_1") (pintype "passive"))
      (node (ref "C59") (pin "1") (pinfunction "1_1") (pintype "passive"))
      (node (ref "C62") (pin "1") (pinfunction "1_1") (pintype "passive"))
      (node (ref "C65") (pin "2") (pinfunction "2_2") (pintype "passive"))
      (node (ref "C66") (pin "1") (pinfunction "1_1") (pintype "passive"))
      (node (ref "FB5") (pin "1") (pinfunction "1_1") (pintype "passive"))
      (node (ref "FB7") (pin "1") (pinfunction "1_1") (pintype "passive"))
      (node (ref "IC1") (pin "1") (pinfunction "A0_1") (pintype "input"))
      (node (ref "IC1") (pin "2") (pinfunction "A1_2") (pintype "input"))
      (node (ref "IC1") (pin "3") (pinfunction "A2_3") (pintype "input"))
      (node (ref "IC1") (pin "4") (pinfunction "GND_4") (pintype "passive"))
      (node (ref "IC2") (pin "1") (pinfunction "A0_1") (pintype "input"))
      (node (ref "IC2") (pin "2") (pinfunction "A1_2") (pintype "input"))
      (node (ref "IC2") (pin "3") (pinfunction "A2_3") (pintype "input"))
      (node (ref "IC2") (pin "4") (pinfunction "GND_4") (pintype "passive"))
      (node (ref "JP3") (pin "1") (pinfunction "1_1") (pintype "passive"))
      (node (ref "LED4") (pin "2") (pinfunction "K_2") (pintype "passive"))
      (node (ref "P1") (pin "1") (pinfunction "1_1") (pintype "passive"))
      (node (ref "R14") (pin "1") (pinfunction "1_1") (pintype "passive"))
      (node (ref "R16") (pin "2") (pinfunction "2_2") (pintype "passive"))
      (node (ref "R17") (pin "2") (pinfunction "2_2") (pintype "passive"))
      (node (ref "R18") (pin "2") (pinfunction "2_2") (pintype "passive"))
      (node (ref "R19") (pin "1") (pinfunction "1_1") (pintype "passive"))
      (node (ref "R6") (pin "2") (pinfunction "2_2") (pintype "passive"))
      (node (ref "R7") (pin "2") (pinfunction "2_2") (pintype "passive"))
      (node (ref "SW1") (pin "2") (pinfunction "2_2") (pintype "passive"))
      (node (ref "SW2") (pin "2") (pinfunction "2_2") (pintype "passive"))
      (node (ref "SW3") (pin "1") (pinfunction "1_1") (pintype "passive"))
      (node (ref "U1") (pin "4") (pinfunction "VSS_4") (pintype "power_in"))
      (node (ref "U2") (pin "0") (pinfunction "GND_0") (pintype "passive"))
      (node (ref "U4") (pin "2") (pinfunction "GND_2") (pintype "passive"))
      (node (ref "U5") (pin "3") (pinfunction "VSSA_3") (pintype "passive"))
      (node (ref "U6") (pin "0") (pinfunction "GND_0") (pintype "passive"))
      (node (ref "U6") (pin "2") (pinfunction "GND_2") (pintype "passive"))
      (node (ref "U8") (pin "2") (pinfunction "GND_2") (pintype "passive"))
      (node (ref "USBC1") (pin "0") (pinfunction "0_0") (pintype "passive"))
      (node (ref "USBC1") (pin "A1") (pinfunction "GND_A1") (pintype "passive"))
      (node (ref "USBC1") (pin "A12") (pinfunction "GND_A12") (pintype "passive"))
      (node (ref "USBC1") (pin "B1") (pinfunction "GND_B1") (pintype "passive"))
      (node (ref "USBC1") (pin "B12") (pinfunction "GND_B12") (pintype "passive"))
      (node (ref "UWB1") (pin "16") (pinfunction "VSS_16") (pintype "passive"))
      (node (ref "UWB1") (pin "21") (pinfunction "VSS_21") (pintype "passive"))
      (node (ref "UWB1") (pin "23") (pinfunction "VSS_23") (pintype "passive"))
      (node (ref "UWB1") (pin "24") (pinfunction "VSS_24") (pintype "passive"))
      (node (ref "UWB1") (pin "8") (pinfunction "VSS_8") (pintype "passive"))
      (node (ref "X1") (pin "2") (pinfunction "GND_2") (pintype "passive"))
      (node (ref "X2") (pin "2") (pinfunction "2_2") (pintype "passive"))
      (node (ref "X2") (pin "4") (pinfunction "4_4") (pintype "passive"))
    )
    (net (code "32") (name "GNDA") (class "Default")
      (node (ref "C44") (pin "1") (pinfunction "1_1") (pintype "passive"))
      (node (ref "C45") (pin "1") (pinfunction "1_1") (pintype "passive"))
      (node (ref "C52") (pin "1") (pinfunction "1_1") (pintype "passive"))
      (node (ref "C55") (pin "1") (pinfunction "1_1") (pintype "passive"))
      (node (ref "C57") (pin "1") (pinfunction "1_1") (pintype "passive"))
      (node (ref "C58") (pin "1") (pinfunction "1_1") (pintype "passive"))
      (node (ref "C67") (pin "1") (pinfunction "1_1") (pintype "passive"))
      (node (ref "C68") (pin "1") (pinfunction "1_1") (pintype "passive"))
      (node (ref "FB7") (pin "2") (pinfunction "2_2") (pintype "passive"))
      (node (ref "U5") (pin "27") (pinfunction "GND_HP_27") (pintype "passive"))
      (node (ref "U5") (pin "36") (pinfunction "AVSS_36") (pintype "passive"))
      (node (ref "U5") (pin "44") (pinfunction "GNDCP_44") (pintype "passive"))
    )
    (net (code "33") (name "GNDRF") (class "Default")
      (node (ref "BK1") (pin "33") (pinfunction "33_33") (pintype "passive"))
      (node (ref "C17") (pin "2") (pinfunction "2_2") (pintype "passive"))
      (node (ref "C18") (pin "2") (pinfunction "2_2") (pintype "passive"))
      (node (ref "C19") (pin "2") (pinfunction "2_2") (pintype "passive"))
      (node (ref "C2") (pin "1") (pinfunction "1_1") (pintype "passive"))
      (node (ref "C20") (pin "2") (pinfunction "2_2") (pintype "passive"))
      (node (ref "C21") (pin "2") (pinfunction "2_2") (pintype "passive"))
      (node (ref "C23") (pin "1") (pinfunction "1_1") (pintype "passive"))
      (node (ref "C25") (pin "2") (pinfunction "2_2") (pintype "passive"))
      (node (ref "C3") (pin "1") (pinfunction "1_1") (pintype "passive"))
      (node (ref "C31") (pin "1") (pinfunction "1_1") (pintype "passive"))
      (node (ref "C32") (pin "1") (pinfunction "1_1") (pintype "passive"))
      (node (ref "C33") (pin "1") (pinfunction "1_1") (pintype "passive"))
      (node (ref "C34") (pin "2") (pinfunction "2_2") (pintype "passive"))
      (node (ref "C35") (pin "2") (pinfunction "2_2") (pintype "passive"))
      (node (ref "C36") (pin "2") (pinfunction "2_2") (pintype "passive"))
      (node (ref "C37") (pin "1") (pinfunction "1_1") (pintype "passive"))
      (node (ref "C5") (pin "1") (pinfunction "1_1") (pintype "passive"))
      (node (ref "C6") (pin "1") (pinfunction "1_1") (pintype "passive"))
      (node (ref "C7") (pin "1") (pinfunction "1_1") (pintype "passive"))
      (node (ref "C8") (pin "1") (pinfunction "1_1") (pintype "passive"))
      (node (ref "FB5") (pin "2") (pinfunction "2_2") (pintype "passive"))
      (node (ref "JP1") (pin "2") (pinfunction "GND_2") (pintype "passive"))
      (node (ref "JP1") (pin "3") (pinfunction "GND_3") (pintype "passive"))
      (node (ref "JP2") (pin "2") (pinfunction "GND_2") (pintype "passive"))
      (node (ref "JP2") (pin "3") (pinfunction "GND_3") (pintype "passive"))
      (node (ref "L5") (pin "1") (pinfunction "1_1") (pintype "passive"))
      (node (ref "R15") (pin "1") (pinfunction "1_1") (pintype "passive"))
      (node (ref "U3") (pin "2") (pinfunction "GND_2") (pintype "passive"))
    )
    (net (code "34") (name "Net-(BK1-EXCN)") (class "Default")
      (node (ref "BK1") (pin "12") (pinfunction "EXCN_12") (pintype "passive"))
      (node (ref "C22") (pin "2") (pinfunction "2_2") (pintype "passive"))
    )
    (net (code "35") (name "Net-(BK1-EXCP)") (class "Default")
      (node (ref "BK1") (pin "11") (pinfunction "EXCP_11") (pintype "passive"))
      (node (ref "C22") (pin "1") (pinfunction "1_1") (pintype "passive"))
    )
    (net (code "36") (name "Net-(BK1-TXON)") (class "Default")
      (node (ref "BK1") (pin "9") (pinfunction "TXON_9") (pintype "passive"))
      (node (ref "C10") (pin "1") (pinfunction "1_1") (pintype "passive"))
      (node (ref "L1") (pin "1") (pinfunction "1_1") (pintype "passive"))
    )
    (net (code "37") (name "Net-(BK1-TXOP)") (class "Default")
      (node (ref "BK1") (pin "10") (pinfunction "TXOP_10") (pintype "passive"))
      (node (ref "C16") (pin "1") (pinfunction "1_1") (pintype "passive"))
      (node (ref "L2") (pin "1") (pinfunction "1_1") (pintype "passive"))
    )
    (net (code "38") (name "Net-(BK1-VCCTX)") (class "Default")
      (node (ref "BK1") (pin "7") (pinfunction "VCCTX_7") (pintype "passive"))
      (node (ref "FB1") (pin "2") (pinfunction "2_2") (pintype "passive"))
    )
    (net (code "39") (name "Net-(BK1-VDDDIG)") (class "Default")
      (node (ref "BK1") (pin "17") (pinfunction "VDDDIG_17") (pintype "passive"))
      (node (ref "C32") (pin "2") (pinfunction "2_2") (pintype "passive"))
    )
    (net (code "40") (name "Net-(BK1-VDDVCO)") (class "Default")
      (node (ref "BK1") (pin "1") (pinfunction "VDDVCO_1") (pintype "passive"))
      (node (ref "C7") (pin "2") (pinfunction "2_2") (pintype "passive"))
    )
    (net (code "41") (name "Net-(BK1-XI)") (class "Default")
      (node (ref "BK1") (pin "31") (pinfunction "XI_31") (pintype "passive"))
      (node (ref "C20") (pin "1") (pinfunction "1_1") (pintype "passive"))
      (node (ref "X3") (pin "1") (pinfunction "1_1") (pintype "passive"))
    )
    (net (code "42") (name "Net-(BK1-XO)") (class "Default")
      (node (ref "BK1") (pin "30") (pinfunction "XO_30") (pintype "passive"))
      (node (ref "C21") (pin "1") (pinfunction "1_1") (pintype "passive"))
      (node (ref "X3") (pin "2") (pinfunction "2_2") (pintype "passive"))
    )
    (net (code "43") (name "Net-(C2-Pad2)") (class "Default")
      (node (ref "C2") (pin "2") (pinfunction "2_2") (pintype "passive"))
      (node (ref "C3") (pin "2") (pinfunction "2_2") (pintype "passive"))
      (node (ref "FB1") (pin "1") (pinfunction "1_1") (pintype "passive"))
      (node (ref "L1") (pin "2") (pinfunction "2_2") (pintype "passive"))
      (node (ref "L2") (pin "2") (pinfunction "2_2") (pintype "passive"))
    )
    (net (code "44") (name "Net-(C10-Pad2)") (class "Default")
      (node (ref "C10") (pin "2") (pinfunction "2_2") (pintype "passive"))
      (node (ref "C8") (pin "2") (pinfunction "2_2") (pintype "passive"))
      (node (ref "L4") (pin "2") (pinfunction "2_2") (pintype "passive"))
    )
    (net (code "45") (name "Net-(C15-Pad1)") (class "Default")
      (node (ref "C15") (pin "1") (pinfunction "1_1") (pintype "passive"))
      (node (ref "C16") (pin "2") (pinfunction "2_2") (pintype "passive"))
      (node (ref "L5") (pin "2") (pinfunction "2_2") (pintype "passive"))
    )
    (net (code "46") (name "Net-(C15-Pad2)") (class "Default")
      (node (ref "C15") (pin "2") (pinfunction "2_2") (pintype "passive"))
      (node (ref "C9") (pin "1") (pinfunction "1_1") (pintype "passive"))
      (node (ref "L4") (pin "1") (pinfunction "1_1") (pintype "passive"))
    )
    (net (code "47") (name "Net-(IC1-SCL)") (class "Default")
      (node (ref "IC1") (pin "6") (pinfunction "SCL_6") (pintype "input"))
      (node (ref "R23") (pin "1") (pinfunction "1_1") (pintype "passive"))
      (node (ref "U5") (pin "18") (pinfunction "I2C_SCL_18") (pintype "passive"))
    )
    (net (code "48") (name "Net-(IC1-SDA)") (class "Default")
      (node (ref "IC1") (pin "5") (pinfunction "SDA_5") (pintype "bidirectional"))
      (node (ref "R24") (pin "1") (pinfunction "1_1") (pintype "passive"))
      (node (ref "U5") (pin "19") (pinfunction "I2C_SDA_19") (pintype "passive"))
    )
    (net (code "49") (name "Net-(JP1-ANT)") (class "Default")
      (node (ref "C18") (pin "1") (pinfunction "1_1") (pintype "passive"))
      (node (ref "C9") (pin "2") (pinfunction "2_2") (pintype "passive"))
      (node (ref "JP1") (pin "1") (pinfunction "ANT_1") (pintype "passive"))
      (node (ref "R25") (pin "1") (pinfunction "1_1") (pintype "passive"))
    )
    (net (code "50") (name "Net-(JP2-ANT)") (class "Default")
      (node (ref "C17") (pin "1") (pinfunction "1_1") (pintype "passive"))
      (node (ref "JP2") (pin "1") (pinfunction "ANT_1") (pintype "passive"))
      (node (ref "R25") (pin "2") (pinfunction "2_2") (pintype "passive"))
    )
    (net (code "51") (name "Net-(LED1-A)") (class "Default")
      (node (ref "LED1") (pin "1") (pinfunction "A_1") (pintype "passive"))
      (node (ref "R5") (pin "1") (pinfunction "1_1") (pintype "passive"))
    )
    (net (code "52") (name "Net-(LED2-A)") (class "Default")
      (node (ref "LED2") (pin "1") (pinfunction "A_1") (pintype "passive"))
      (node (ref "R2") (pin "1") (pinfunction "1_1") (pintype "passive"))
    )
    (net (code "53") (name "Net-(LED3-A)") (class "Default")
      (node (ref "LED3") (pin "1") (pinfunction "A_1") (pintype "passive"))
      (node (ref "UWB1") (pin "13") (pinfunction "GPIO2_13") (pintype "passive"))
    )
    (net (code "54") (name "Net-(LED3-K)") (class "Default")
      (node (ref "LED3") (pin "2") (pinfunction "K_2") (pintype "passive"))
      (node (ref "R7") (pin "1") (pinfunction "1_1") (pintype "passive"))
    )
    (net (code "55") (name "Net-(LED4-A)") (class "Default")
      (node (ref "LED4") (pin "1") (pinfunction "A_1") (pintype "passive"))
      (node (ref "R22") (pin "1") (pinfunction "1_1") (pintype "passive"))
    )
    (net (code "56") (name "Net-(LED5-A)") (class "Default")
      (node (ref "LED5") (pin "1") (pinfunction "A_1") (pintype "passive"))
      (node (ref "UWB1") (pin "12") (pinfunction "GPIO3_12") (pintype "passive"))
    )
    (net (code "57") (name "Net-(LED5-K)") (class "Default")
      (node (ref "LED5") (pin "2") (pinfunction "K_2") (pintype "passive"))
      (node (ref "R16") (pin "1") (pinfunction "1_1") (pintype "passive"))
    )
    (net (code "58") (name "Net-(U1-PB3)") (class "Default")
      (node (ref "C1") (pin "2") (pinfunction "2_2") (pintype "passive"))
      (node (ref "SW1") (pin "1") (pinfunction "1_1") (pintype "passive"))
      (node (ref "U1") (pin "23") (pinfunction "PB3_23") (pintype "bidirectional"))
    )
    (net (code "59") (name "Net-(U1-PB4)") (class "Default")
      (node (ref "C4") (pin "2") (pinfunction "2_2") (pintype "passive"))
      (node (ref "SW2") (pin "1") (pinfunction "1_1") (pintype "passive"))
      (node (ref "U1") (pin "24") (pinfunction "PB4_24") (pintype "bidirectional"))
    )
    (net (code "60") (name "Net-(U1-PC14-OSC32_IN)") (class "Default")
      (node (ref "R4") (pin "1") (pinfunction "1_1") (pintype "passive"))
      (node (ref "U1") (pin "1") (pinfunction "PC14-OSC32_IN_1") (pintype "bidirectional"))
    )
    (net (code "61") (name "Net-(U2-XI)") (class "Default")
      (node (ref "U2") (pin "2") (pinfunction "XI_2") (pintype "passive"))
      (node (ref "X2") (pin "3") (pinfunction "3_3") (pintype "passive"))
    )
    (net (code "62") (name "Net-(U2-XO)") (class "Default")
      (node (ref "U2") (pin "1") (pinfunction "XO_1") (pintype "passive"))
      (node (ref "X2") (pin "1") (pinfunction "1_1") (pintype "passive"))
    )
    (net (code "63") (name "Net-(U4-FB)") (class "Default")
      (node (ref "C46") (pin "2") (pinfunction "2_2") (pintype "passive"))
      (node (ref "R13") (pin "1") (pinfunction "1_1") (pintype "passive"))
      (node (ref "R14") (pin "2") (pinfunction "2_2") (pintype "passive"))
      (node (ref "U4") (pin "5") (pinfunction "FB_5") (pintype "passive"))
    )
    (net (code "64") (name "Net-(U4-LX)") (class "Default")
      (node (ref "L3") (pin "1") (pinfunction "1_1") (pintype "passive"))
      (node (ref "U4") (pin "3") (pinfunction "LX_3") (pintype "passive"))
    )
    (net (code "65") (name "Net-(U5-CFLYN)") (class "Default")
      (node (ref "C48") (pin "1") (pinfunction "1_1") (pintype "passive"))
      (node (ref "U5") (pin "43") (pinfunction "CFLYN_43") (pintype "passive"))
    )
    (net (code "66") (name "Net-(U5-CFLYP)") (class "Default")
      (node (ref "C48") (pin "2") (pinfunction "2_2") (pintype "passive"))
      (node (ref "U5") (pin "45") (pinfunction "CFLYP_45") (pintype "passive"))
    )
    (net (code "67") (name "Net-(U5-HPVDD)") (class "Default")
      (node (ref "C55") (pin "2") (pinfunction "2_2") (pintype "passive"))
      (node (ref "U5") (pin "40") (pinfunction "HPVDD_40") (pintype "passive"))
      (node (ref "U5") (pin "41") (pinfunction "VCPP_41") (pintype "passive"))
    )
    (net (code "68") (name "Net-(U5-HPVSS)") (class "Default")
      (node (ref "C52") (pin "2") (pinfunction "2_2") (pintype "passive"))
      (node (ref "U5") (pin "37") (pinfunction "HPVSS_37") (pintype "passive"))
      (node (ref "U5") (pin "42") (pinfunction "VCPN_42") (pintype "passive"))
    )
    (net (code "69") (name "Net-(U5-LEDO)") (class "Default")
      (node (ref "R22") (pin "2") (pinfunction "2_2") (pintype "passive"))
      (node (ref "U5") (pin "8") (pinfunction "LEDO_8") (pintype "passive"))
    )
    (net (code "70") (name "Net-(U5-TEST)") (class "Default")
      (node (ref "R18") (pin "1") (pinfunction "1_1") (pintype "passive"))
      (node (ref "U5") (pin "47") (pinfunction "TEST_47") (pintype "passive"))
    )
    (net (code "71") (name "Net-(U5-V12)") (class "Default")
      (node (ref "C53") (pin "2") (pinfunction "2_2") (pintype "passive"))
      (node (ref "U5") (pin "4") (pinfunction "V12_4") (pintype "passive"))
    )
    (net (code "72") (name "Net-(U5-VMID)") (class "Default")
      (node (ref "C57") (pin "2") (pinfunction "2_2") (pintype "passive"))
      (node (ref "C58") (pin "2") (pinfunction "2_2") (pintype "passive"))
      (node (ref "U5") (pin "35") (pinfunction "VMID_35") (pintype "passive"))
    )
    (net (code "73") (name "Net-(U6-V3)") (class "Default")
      (node (ref "C59") (pin "2") (pinfunction "2_2") (pintype "passive"))
      (node (ref "U6") (pin "6") (pinfunction "V3_6") (pintype "passive"))
    )
    (net (code "74") (name "Net-(USBC1-CC1)") (class "Default")
      (node (ref "R19") (pin "2") (pinfunction "2_2") (pintype "passive"))
      (node (ref "USBC1") (pin "A5") (pinfunction "CC1_A5") (pintype "passive"))
    )
    (net (code "75") (name "Net-(USBC1-CC2)") (class "Default")
      (node (ref "R17") (pin "1") (pinfunction "1_1") (pintype "passive"))
      (node (ref "USBC1") (pin "B5") (pinfunction "CC2_B5") (pintype "passive"))
    )
    (net (code "76") (name "Net-(UWB1-SYNC)") (class "Default")
      (node (ref "R20") (pin "2") (pinfunction "2_2") (pintype "passive"))
      (node (ref "UWB1") (pin "4") (pinfunction "SYNC_4") (pintype "passive"))
    )
    (net (code "77") (name "Net-(X1-OUT)") (class "Default")
      (node (ref "R4") (pin "2") (pinfunction "2_2") (pintype "passive"))
      (node (ref "X1") (pin "3") (pinfunction "OUT_3") (pintype "passive"))
    )
    (net (code "78") (name "Net-(X1-VCC)") (class "Default")
      (node (ref "C26") (pin "2") (pinfunction "2_2") (pintype "passive"))
      (node (ref "C30") (pin "2") (pinfunction "2_2") (pintype "passive"))
      (node (ref "FB8") (pin "1") (pinfunction "1_1") (pintype "passive"))
      (node (ref "X1") (pin "4") (pinfunction "VCC_4") (pintype "passive"))
    )
    (net (code "79") (name "RF3V3") (class "Default")
      (node (ref "BK1") (pin "13") (pinfunction "VCCAUD_13") (pintype "passive"))
      (node (ref "BK1") (pin "16") (pinfunction "VCCDIG_16") (pintype "passive"))
      (node (ref "BK1") (pin "2") (pinfunction "VCCVCO_2") (pintype "passive"))
      (node (ref "BK1") (pin "24") (pinfunction "VCCIF_24") (pintype "passive"))
      (node (ref "BK1") (pin "28") (pinfunction "VCCDVCO_28") (pintype "passive"))
      (node (ref "BK1") (pin "29") (pinfunction "VCCXTAL_29") (pintype "passive"))
      (node (ref "BK1") (pin "32") (pinfunction "VCCPLL_32") (pintype "passive"))
      (node (ref "BK1") (pin "4") (pinfunction "VCCB_4") (pintype "passive"))
      (node (ref "BK1") (pin "8") (pinfunction "VCCPA_8") (pintype "passive"))
      (node (ref "C19") (pin "1") (pinfunction "1_1") (pintype "passive"))
      (node (ref "C23") (pin "2") (pinfunction "2_2") (pintype "passive"))
      (node (ref "C25") (pin "1") (pinfunction "1_1") (pintype "passive"))
      (node (ref "C31") (pin "2") (pinfunction "2_2") (pintype "passive"))
      (node (ref "C33") (pin "2") (pinfunction "2_2") (pintype "passive"))
      (node (ref "C35") (pin "1") (pinfunction "1_1") (pintype "passive"))
      (node (ref "C36") (pin "1") (pinfunction "1_1") (pintype "passive"))
      (node (ref "C37") (pin "2") (pinfunction "2_2") (pintype "passive"))
      (node (ref "C5") (pin "2") (pinfunction "2_2") (pintype "passive"))
      (node (ref "C6") (pin "2") (pinfunction "2_2") (pintype "passive"))
      (node (ref "U3") (pin "5") (pinfunction "VOUT_5") (pintype "passive"))
    )
    (net (code "80") (name "USB_5V") (class "Default")
      (node (ref "C27") (pin "2") (pinfunction "2_2") (pintype "passive"))
      (node (ref "C34") (pin "1") (pinfunction "1_1") (pintype "passive"))
      (node (ref "C39") (pin "2") (pinfunction "2_2") (pintype "passive"))
      (node (ref "C43") (pin "1") (pinfunction "1_1") (pintype "passive"))
      (node (ref "C47") (pin "1") (pinfunction "1_1") (pintype "passive"))
      (node (ref "FB4") (pin "1") (pinfunction "1_1") (pintype "passive"))
      (node (ref "U2") (pin "15") (pinfunction "V5_15") (pintype "passive"))
      (node (ref "U3") (pin "1") (pinfunction "VIN_1") (pintype "passive"))
      (node (ref "U4") (pin "1") (pinfunction "EN_1") (pintype "passive"))
      (node (ref "U4") (pin "4") (pinfunction "VIN_4") (pintype "passive"))
      (node (ref "U5") (pin "1") (pinfunction "VBUS_1") (pintype "passive"))
      (node (ref "U6") (pin "9") (pinfunction "VBUS_9") (pintype "passive"))
    )
    (net (code "81") (name "VBUS") (class "Default")
      (node (ref "C28") (pin "2") (pinfunction "2_2") (pintype "passive"))
      (node (ref "C29") (pin "2") (pinfunction "2_2") (pintype "passive"))
      (node (ref "FB4") (pin "2") (pinfunction "2_2") (pintype "passive"))
      (node (ref "USBC1") (pin "A4") (pinfunction "VBUS_A4") (pintype "passive"))
      (node (ref "USBC1") (pin "A9") (pinfunction "VBUS_A9") (pintype "passive"))
      (node (ref "USBC1") (pin "B4") (pinfunction "VBUS_B4") (pintype "passive"))
      (node (ref "USBC1") (pin "B9") (pinfunction "VBUS_B9") (pintype "passive"))
    )
    (net (code "82") (name "unconnected-(BK1-GPIO2-Pad20)") (class "Default")
      (node (ref "BK1") (pin "20") (pinfunction "GPIO2_20") (pintype "passive+no_connect"))
    )
    (net (code "83") (name "unconnected-(BK1-GPIO4-Pad25)") (class "Default")
      (node (ref "BK1") (pin "25") (pinfunction "GPIO4_25") (pintype "passive+no_connect"))
    )
    (net (code "84") (name "unconnected-(BK1-IRQ-Pad27)") (class "Default")
      (node (ref "BK1") (pin "27") (pinfunction "IRQ_27") (pintype "passive+no_connect"))
    )
    (net (code "85") (name "unconnected-(BK1-MICN-Pad14)") (class "Default")
      (node (ref "BK1") (pin "14") (pinfunction "MICN_14") (pintype "passive+no_connect"))
    )
    (net (code "86") (name "unconnected-(BK1-MICP-Pad15)") (class "Default")
      (node (ref "BK1") (pin "15") (pinfunction "MICP_15") (pintype "passive+no_connect"))
    )
    (net (code "87") (name "unconnected-(BK1-NC-Pad5)") (class "Default")
      (node (ref "BK1") (pin "5") (pinfunction "NC_5") (pintype "passive"))
    )
    (net (code "88") (name "unconnected-(BK1-NC-Pad6)") (class "Default")
      (node (ref "BK1") (pin "6") (pinfunction "NC_6") (pintype "passive"))
    )
    (net (code "89") (name "unconnected-(BK1-XO2-Pad23)") (class "Default")
      (node (ref "BK1") (pin "23") (pinfunction "XO2_23") (pintype "passive+no_connect"))
    )
    (net (code "90") (name "unconnected-(IC1-WP-Pad7)") (class "Default")
      (node (ref "IC1") (pin "7") (pinfunction "WP_7") (pintype "passive+no_connect"))
    )
    (net (code "91") (name "unconnected-(IC2-WP-Pad7)") (class "Default")
      (node (ref "IC2") (pin "7") (pinfunction "WP_7") (pintype "passive+no_connect"))
    )
    (net (code "92") (name "unconnected-(U1-PA4-Pad10)") (class "Default")
      (node (ref "U1") (pin "10") (pinfunction "PA4_10") (pintype "bidirectional+no_connect"))
    )
    (net (code "93") (name "unconnected-(U1-PA15-Pad22)") (class "Default")
      (node (ref "U1") (pin "22") (pinfunction "PA15_22") (pintype "bidirectional+no_connect"))
    )
    (net (code "94") (name "unconnected-(U1-PB1-Pad15)") (class "Default")
      (node (ref "U1") (pin "15") (pinfunction "PB1_15") (pintype "bidirectional+no_connect"))
    )
    (net (code "95") (name "unconnected-(U1-PB5-Pad25)") (class "Default")
      (node (ref "U1") (pin "25") (pinfunction "PB5_25") (pintype "bidirectional+no_connect"))
    )
    (net (code "96") (name "unconnected-(U1-PC6-Pad17)") (class "Default")
      (node (ref "U1") (pin "17") (pinfunction "PC6_17") (pintype "bidirectional+no_connect"))
    )
    (net (code "97") (name "unconnected-(U2-DM1-Pad9)") (class "Default")
      (node (ref "U2") (pin "9") (pinfunction "DM1_9") (pintype "passive+no_connect"))
    )
    (net (code "98") (name "unconnected-(U2-DM3-Pad5)") (class "Default")
      (node (ref "U2") (pin "5") (pinfunction "DM3_5") (pintype "passive+no_connect"))
    )
    (net (code "99") (name "unconnected-(U2-DP1-Pad10)") (class "Default")
      (node (ref "U2") (pin "10") (pinfunction "DP1_10") (pintype "passive+no_connect"))
    )
    (net (code "100") (name "unconnected-(U2-DP3-Pad6)") (class "Default")
      (node (ref "U2") (pin "6") (pinfunction "DP3_6") (pintype "passive+no_connect"))
    )
    (net (code "101") (name "unconnected-(U2-PGANG-Pad14)") (class "Default")
      (node (ref "U2") (pin "14") (pinfunction "PGANG_14") (pintype "passive+no_connect"))
    )
    (net (code "102") (name "unconnected-(U2-~{RESET}{slash}CDP-Pad13)") (class "Default")
      (node (ref "U2") (pin "13") (pinfunction "~{RESET}/CDP_13") (pintype "passive+no_connect"))
    )
    (net (code "103") (name "unconnected-(U3-NC-Pad4)") (class "Default")
      (node (ref "U3") (pin "4") (pinfunction "NC_4") (pintype "passive+no_connect"))
    )
    (net (code "104") (name "unconnected-(U5-EQ3D_LED-Pad48)") (class "Default")
      (node (ref "U5") (pin "48") (pinfunction "EQ3D_LED_48") (pintype "passive+no_connect"))
    )
    (net (code "105") (name "unconnected-(U5-INSEL-Pad9)") (class "Default")
      (node (ref "U5") (pin "9") (pinfunction "INSEL_9") (pintype "passive+no_connect"))
    )
    (net (code "106") (name "unconnected-(U5-KEY_RENC_INV-Pad7)") (class "Default")
      (node (ref "U5") (pin "7") (pinfunction "KEY_RENC_INV_7") (pintype "passive+no_connect"))
    )
    (net (code "107") (name "unconnected-(U5-LHPOUT-Pad39)") (class "Default")
      (node (ref "U5") (pin "39") (pinfunction "LHPOUT_39") (pintype "passive+no_connect"))
    )
    (net (code "108") (name "unconnected-(U5-MIC1-Pad29)") (class "Default")
      (node (ref "U5") (pin "29") (pinfunction "MIC1_29") (pintype "passive+no_connect"))
    )
    (net (code "109") (name "unconnected-(U5-MIC1N-Pad31)") (class "Default")
      (node (ref "U5") (pin "31") (pinfunction "MIC1N_31") (pintype "passive+no_connect"))
    )
    (net (code "110") (name "unconnected-(U5-MIC1P-Pad32)") (class "Default")
      (node (ref "U5") (pin "32") (pinfunction "MIC1P_32") (pintype "passive+no_connect"))
    )
    (net (code "111") (name "unconnected-(U5-MIC2P-Pad33)") (class "Default")
      (node (ref "U5") (pin "33") (pinfunction "MIC2P_33") (pintype "passive+no_connect"))
    )
    (net (code "112") (name "unconnected-(U5-MICBIAS-Pad30)") (class "Default")
      (node (ref "U5") (pin "30") (pinfunction "MICBIAS_30") (pintype "passive+no_connect"))
    )
    (net (code "113") (name "unconnected-(U5-MSEL-Pad10)") (class "Default")
      (node (ref "U5") (pin "10") (pinfunction "MSEL_10") (pintype "passive+no_connect"))
    )
    (net (code "114") (name "unconnected-(U5-NEXT_TRACK-Pad20)") (class "Default")
      (node (ref "U5") (pin "20") (pinfunction "NEXT_TRACK_20") (pintype "passive+no_connect"))
    )
    (net (code "115") (name "unconnected-(U5-PALY_PAUSE-Pad22)") (class "Default")
      (node (ref "U5") (pin "22") (pinfunction "PALY_PAUSE_22") (pintype "passive+no_connect"))
    )
    (net (code "116") (name "unconnected-(U5-PLAY_EN-Pad16)") (class "Default")
      (node (ref "U5") (pin "16") (pinfunction "PLAY_EN_16") (pintype "passive+no_connect"))
    )
    (net (code "117") (name "unconnected-(U5-PRE_TACK-Pad21)") (class "Default")
      (node (ref "U5") (pin "21") (pinfunction "PRE_TACK_21") (pintype "passive+no_connect"))
    )
    (net (code "118") (name "unconnected-(U5-REC_EN-Pad17)") (class "Default")
      (node (ref "U5") (pin "17") (pinfunction "REC_EN_17") (pintype "passive+no_connect"))
    )
    (net (code "119") (name "unconnected-(U5-RHPOUT-Pad38)") (class "Default")
      (node (ref "U5") (pin "38") (pinfunction "RHPOUT_38") (pintype "passive+no_connect"))
    )
    (net (code "120") (name "unconnected-(U5-RING2-Pad28)") (class "Default")
      (node (ref "U5") (pin "28") (pinfunction "RING2_28") (pintype "passive+no_connect"))
    )
    (net (code "121") (name "unconnected-(U5-SLEEVE-Pad26)") (class "Default")
      (node (ref "U5") (pin "26") (pinfunction "SLEEVE_26") (pintype "passive+no_connect"))
    )
    (net (code "122") (name "unconnected-(U5-STEREO_MIC-Pad13)") (class "Default")
      (node (ref "U5") (pin "13") (pinfunction "STEREO_MIC_13") (pintype "passive+no_connect"))
    )
    (net (code "123") (name "unconnected-(U5-STOP-Pad24)") (class "Default")
      (node (ref "U5") (pin "24") (pinfunction "STOP_24") (pintype "passive+no_connect"))
    )
    (net (code "124") (name "unconnected-(U5-VOLDN-Pad15)") (class "Default")
      (node (ref "U5") (pin "15") (pinfunction "VOLDN_15") (pintype "passive+no_connect"))
    )
    (net (code "125") (name "unconnected-(U5-VP_MUTE-Pad25)") (class "Default")
      (node (ref "U5") (pin "25") (pinfunction "VP_MUTE_25") (pintype "passive+no_connect"))
    )
    (net (code "126") (name "unconnected-(U5-VR_MUTE-Pad23)") (class "Default")
      (node (ref "U5") (pin "23") (pinfunction "VR_MUTE_23") (pintype "passive+no_connect"))
    )
    (net (code "127") (name "unconnected-(U6-CTS-Pad15)") (class "Default")
      (node (ref "U6") (pin "15") (pinfunction "CTS_15") (pintype "passive+no_connect"))
    )
    (net (code "128") (name "unconnected-(U6-DCD-Pad11)") (class "Default")
      (node (ref "U6") (pin "11") (pinfunction "DCD_11") (pintype "passive+no_connect"))
    )
    (net (code "129") (name "unconnected-(U6-DSR-Pad14)") (class "Default")
      (node (ref "U6") (pin "14") (pinfunction "DSR_14") (pintype "passive+no_connect"))
    )
    (net (code "130") (name "unconnected-(U6-DTR-Pad12)") (class "Default")
      (node (ref "U6") (pin "12") (pinfunction "DTR_12") (pintype "passive+no_connect"))
    )
    (net (code "131") (name "unconnected-(U6-RI-Pad16)") (class "Default")
      (node (ref "U6") (pin "16") (pinfunction "RI_16") (pintype "passive+no_connect"))
    )
    (net (code "132") (name "unconnected-(U6-RTS-Pad13)") (class "Default")
      (node (ref "U6") (pin "13") (pinfunction "RTS_13") (pintype "passive+no_connect"))
    )
    (net (code "133") (name "unconnected-(U6-~{ACT}-Pad10)") (class "Default")
      (node (ref "U6") (pin "10") (pinfunction "~{ACT}_10") (pintype "passive+no_connect"))
    )
    (net (code "134") (name "unconnected-(U8-IO1-Pad1)") (class "Default")
      (node (ref "U8") (pin "1") (pinfunction "IO1_1") (pintype "passive+no_connect"))
    )
    (net (code "135") (name "unconnected-(U8-IO4-Pad6)") (class "Default")
      (node (ref "U8") (pin "6") (pinfunction "IO4_6") (pintype "passive+no_connect"))
    )
    (net (code "136") (name "unconnected-(USBC1-SBU1-PadA8)") (class "Default")
      (node (ref "USBC1") (pin "A8") (pinfunction "SBU1_A8") (pintype "passive"))
    )
    (net (code "137") (name "unconnected-(USBC1-SBU2-PadB8)") (class "Default")
      (node (ref "USBC1") (pin "B8") (pinfunction "SBU2_B8") (pintype "passive"))
    )
    (net (code "138") (name "unconnected-(UWB1-EXTON-Pad1)") (class "Default")
      (node (ref "UWB1") (pin "1") (pinfunction "EXTON_1") (pintype "passive+no_connect"))
    )
    (net (code "139") (name "unconnected-(UWB1-GPIO0-Pad15)") (class "Default")
      (node (ref "UWB1") (pin "15") (pinfunction "GPIO0_15") (pintype "passive+no_connect"))
    )
    (net (code "140") (name "unconnected-(UWB1-GPIO1-Pad14)") (class "Default")
      (node (ref "UWB1") (pin "14") (pinfunction "GPIO1_14") (pintype "passive+no_connect"))
    )
    (net (code "141") (name "unconnected-(UWB1-GPIO4-Pad11)") (class "Default")
      (node (ref "UWB1") (pin "11") (pinfunction "GPIO4_11") (pintype "passive+no_connect"))
    )
    (net (code "142") (name "unconnected-(UWB1-GPIO5-Pad10)") (class "Default")
      (node (ref "UWB1") (pin "10") (pinfunction "GPIO5_10") (pintype "passive+no_connect"))
    )
    (net (code "143") (name "unconnected-(UWB1-GPIO6-Pad9)") (class "Default")
      (node (ref "UWB1") (pin "9") (pinfunction "GPIO6_9") (pintype "passive+no_connect"))
    )
    (net (code "144") (name "unconnected-(X1-NC-Pad1)") (class "Default")
      (node (ref "X1") (pin "1") (pinfunction "NC_1") (pintype "passive+no_connect"))
    )
  )
)
